# trill_slim.net
KiCad netlist of a schematic drawn in EAGLE
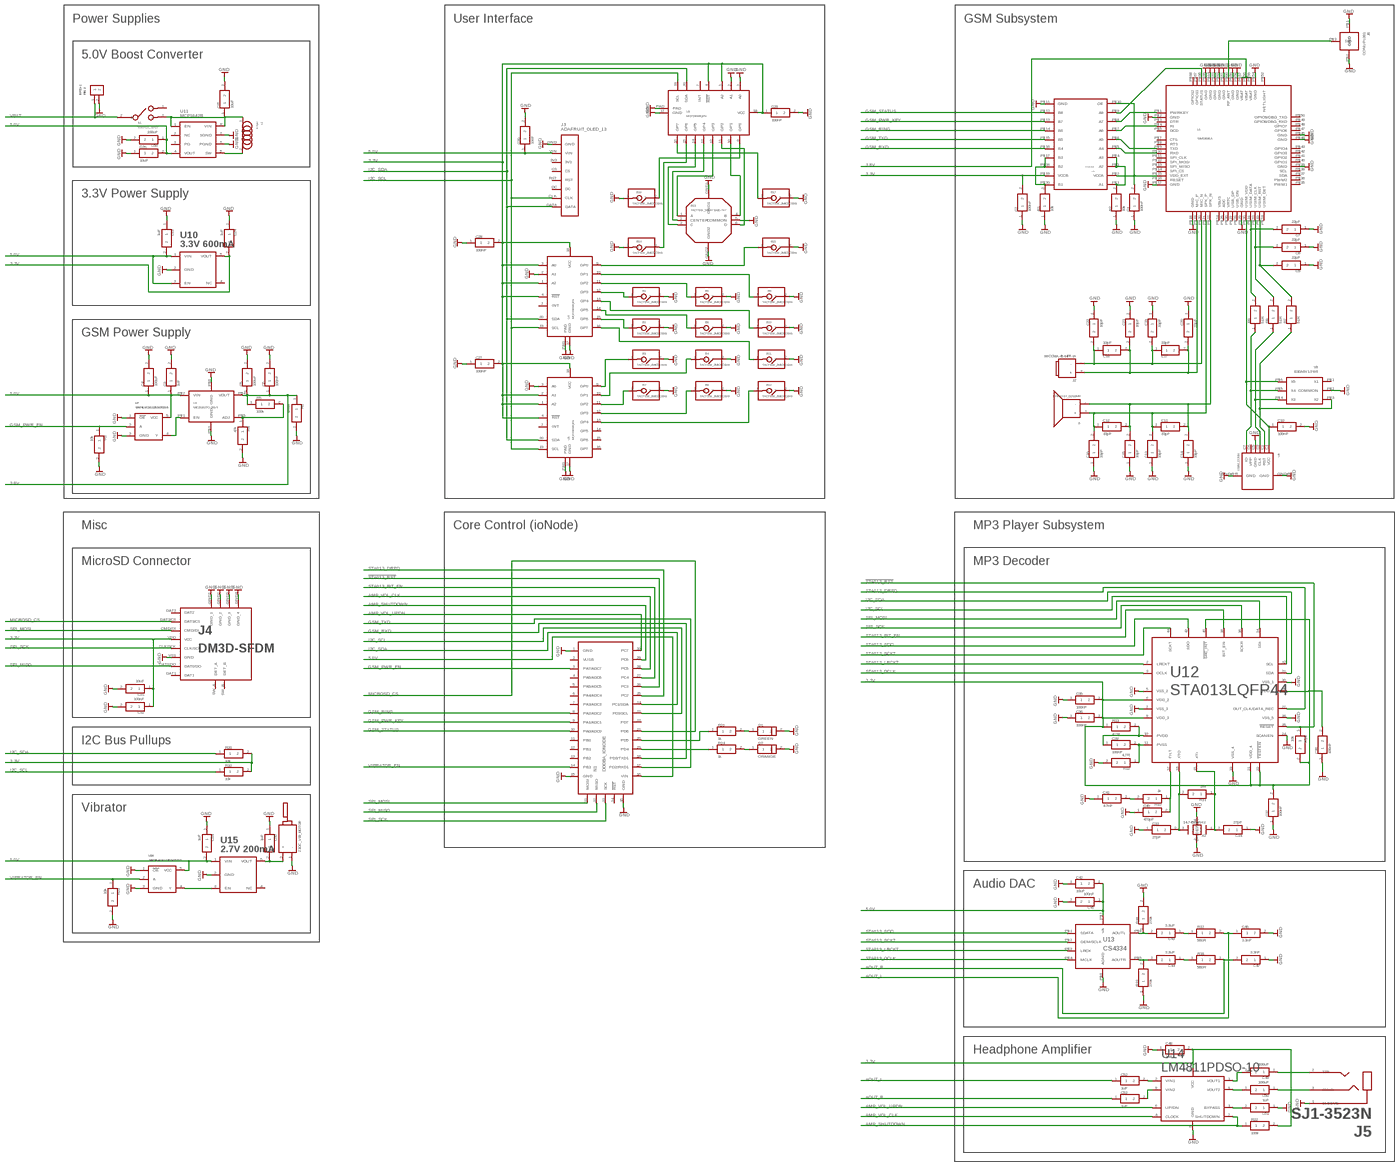
[diagram p0: schematic, sheet 1, overview]
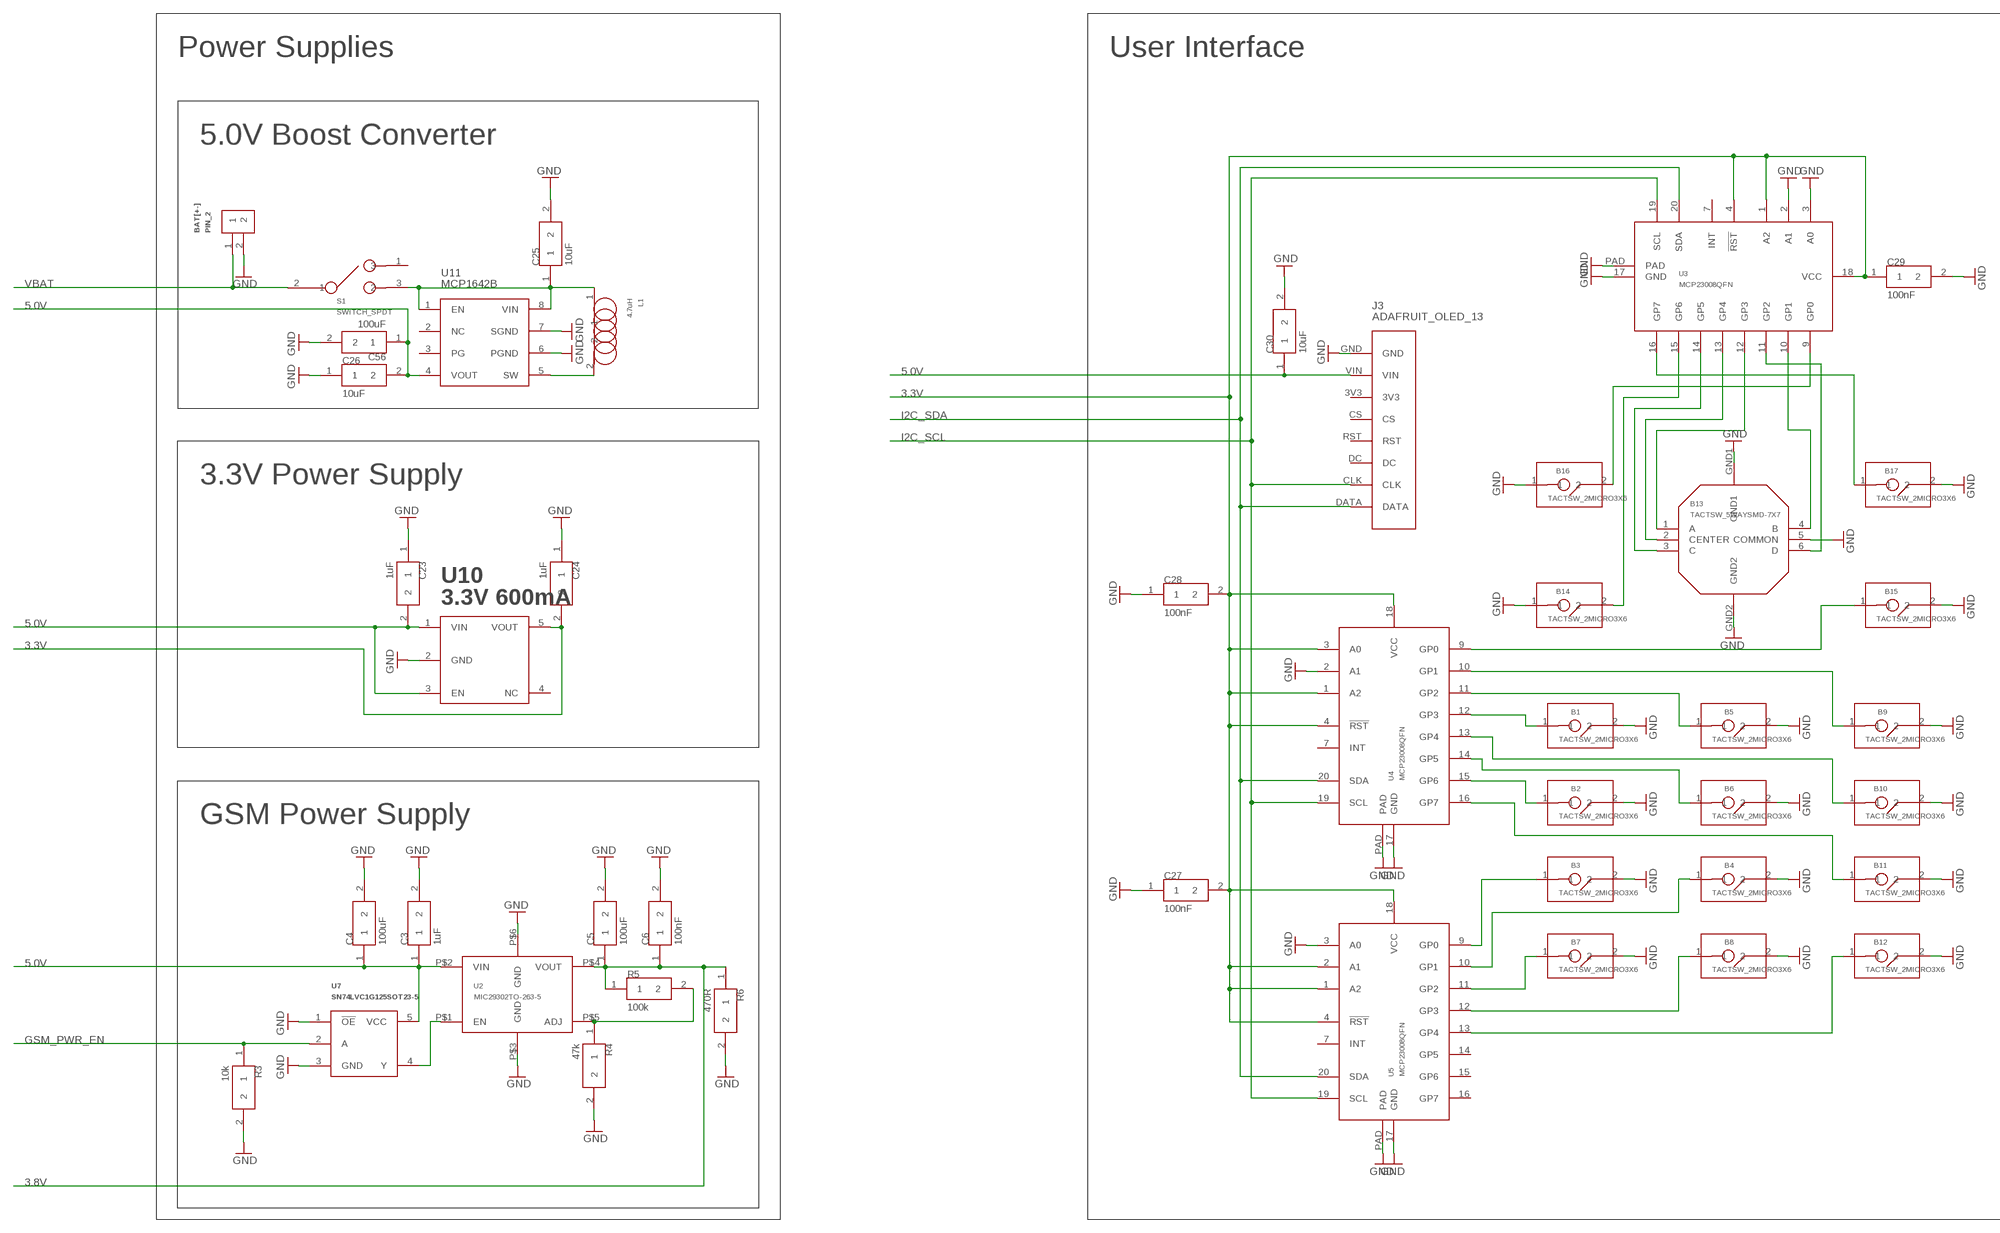
[diagram p1: schematic, sheet 1, part 1 of 4]
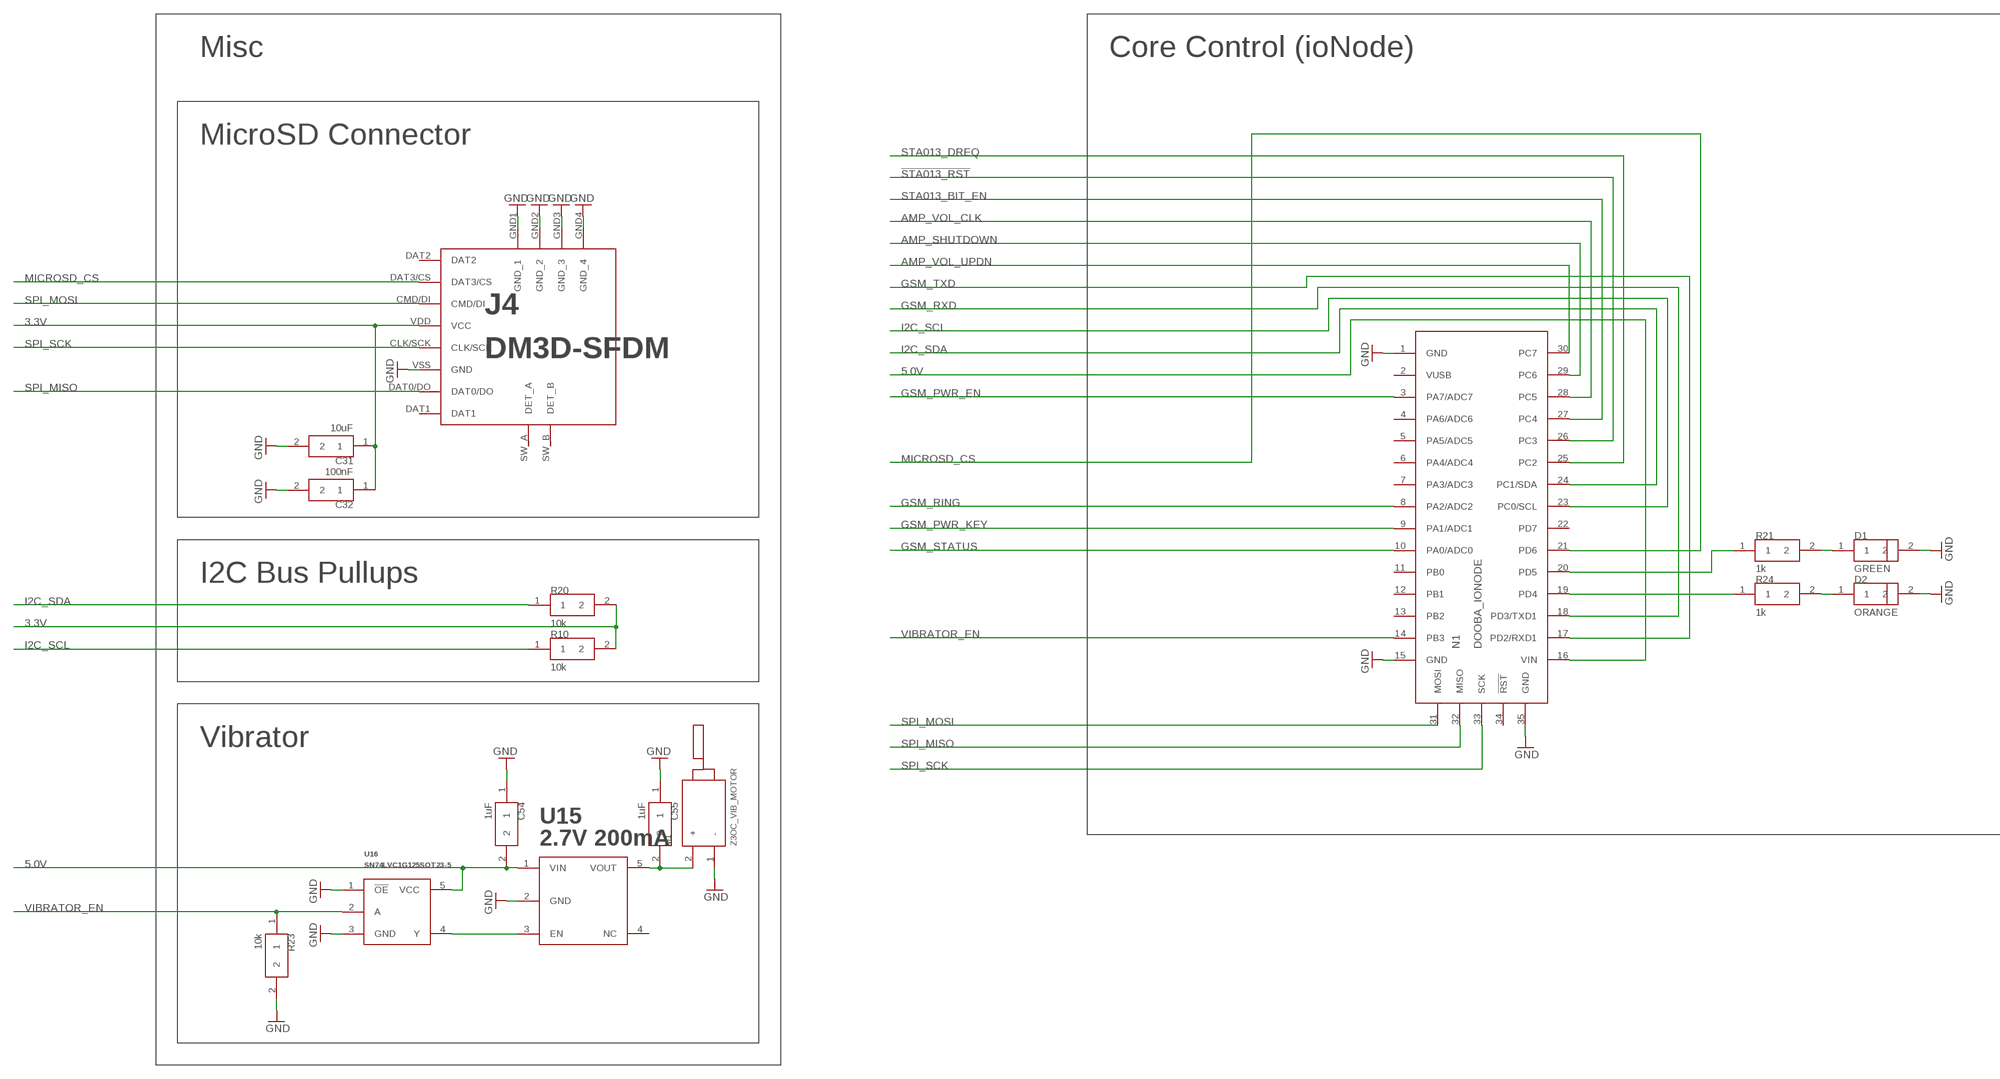
[diagram p2: schematic, sheet 1, part 2 of 4]
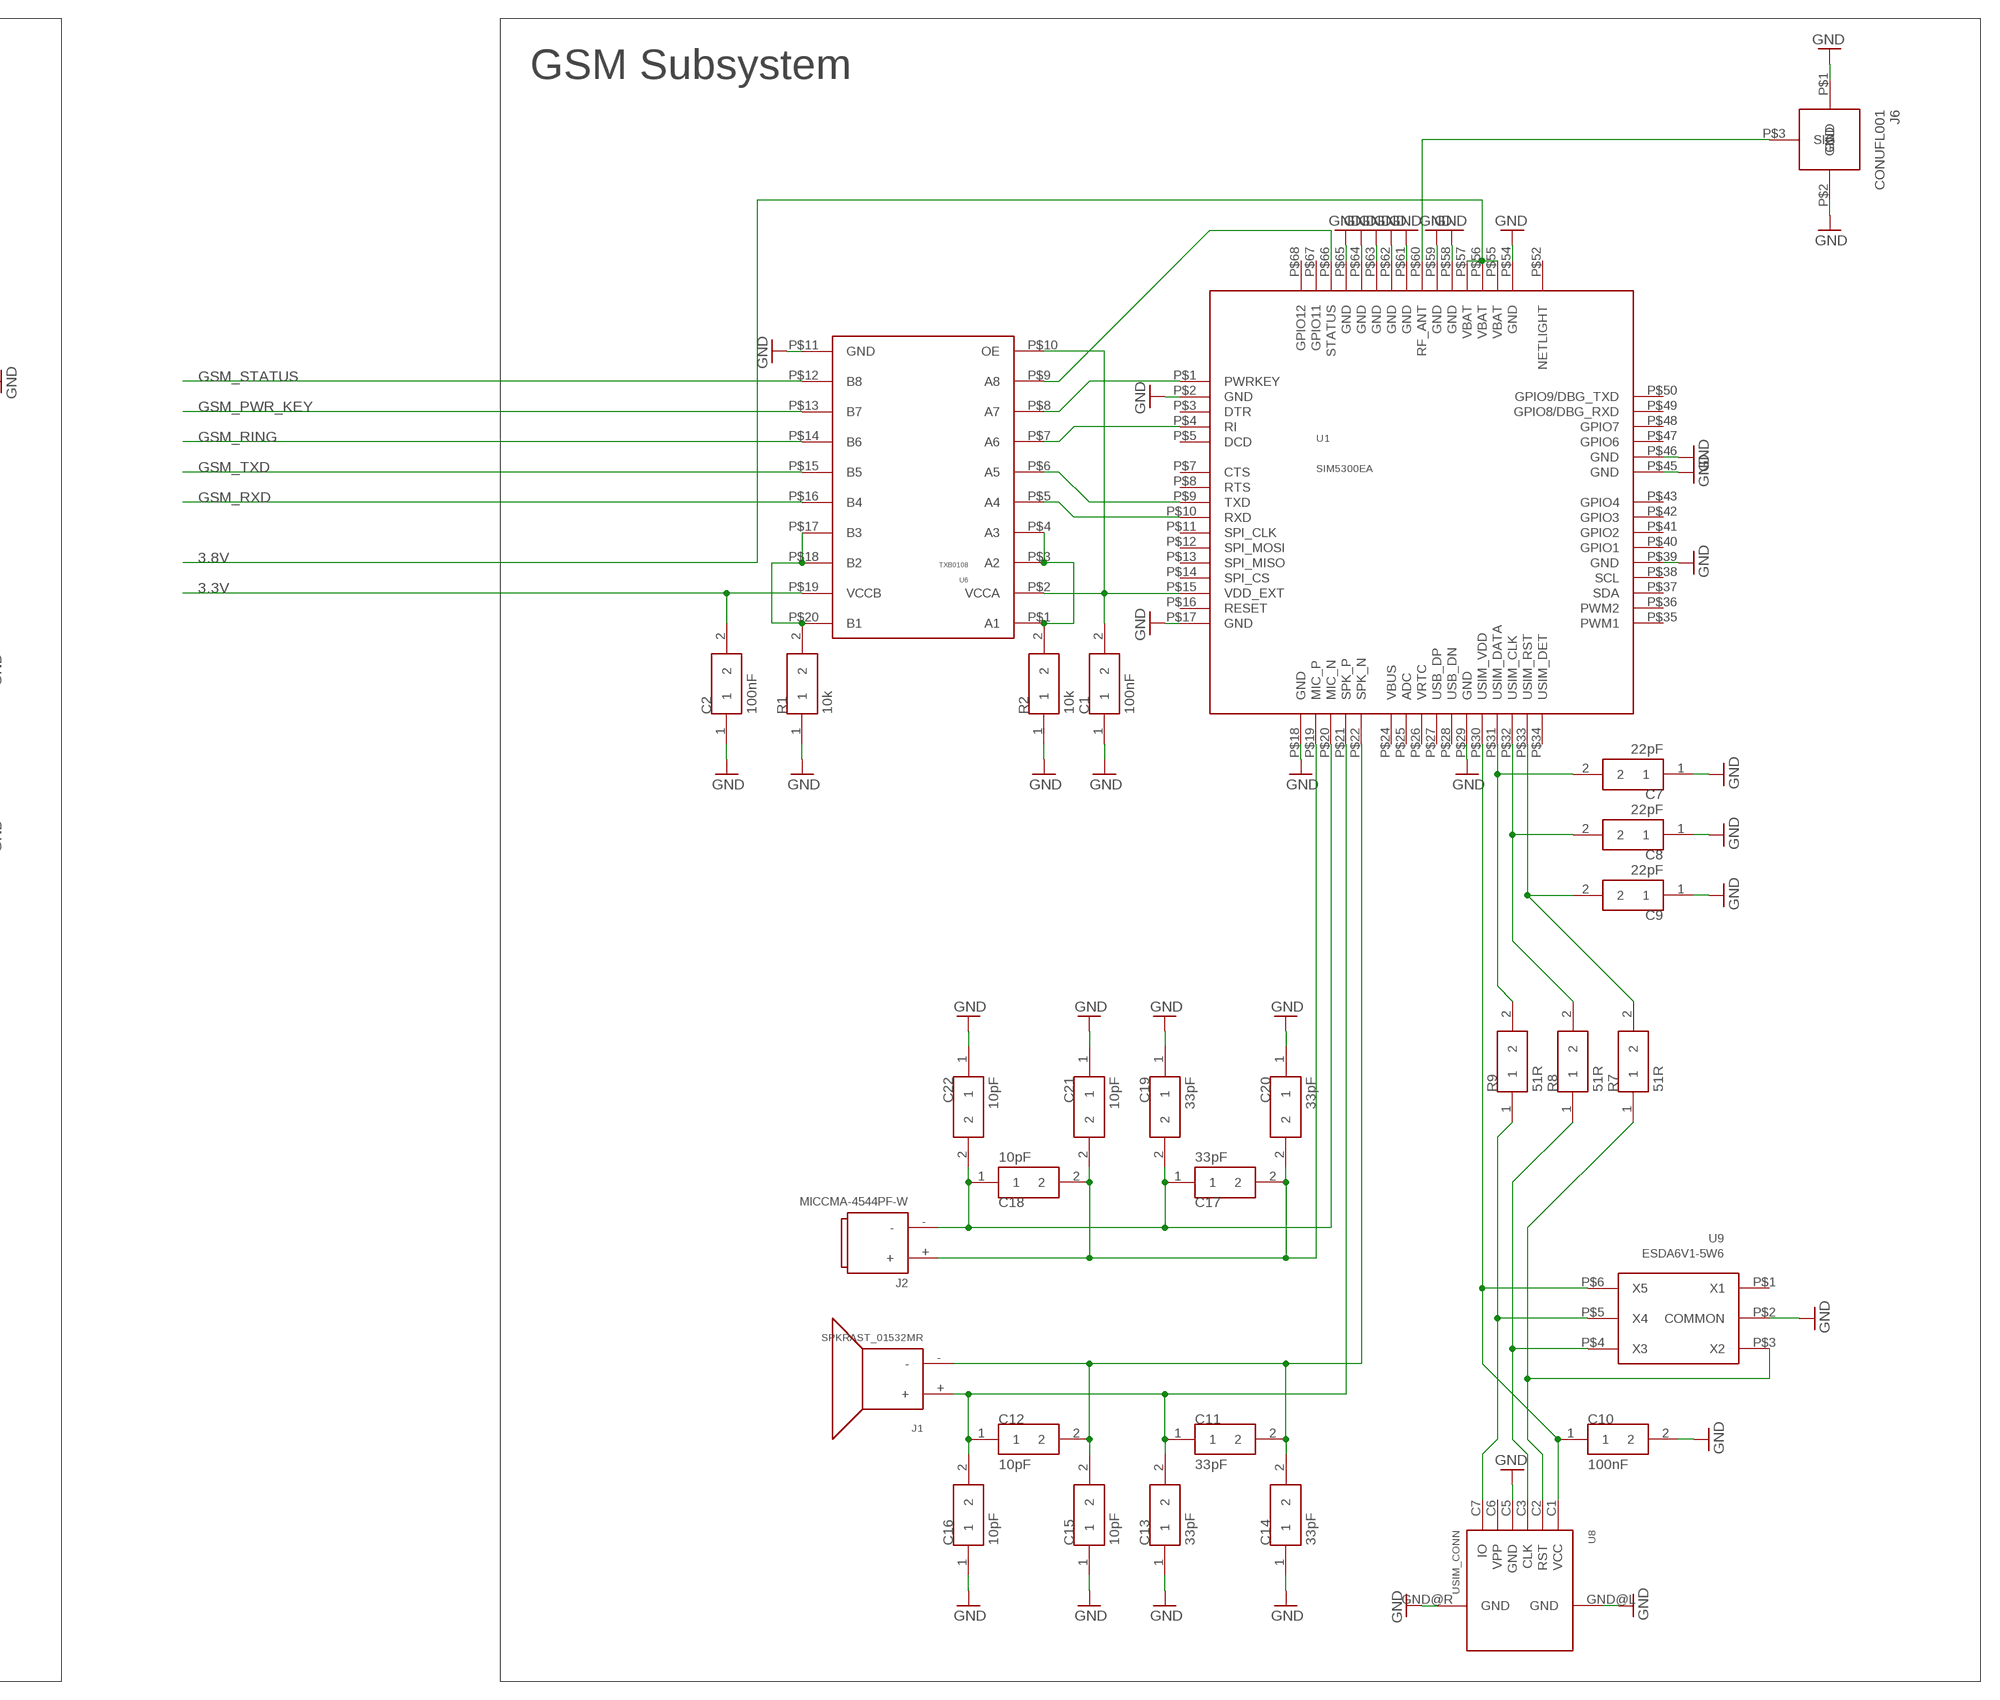
[diagram p3: schematic, sheet 1, part 3 of 4]
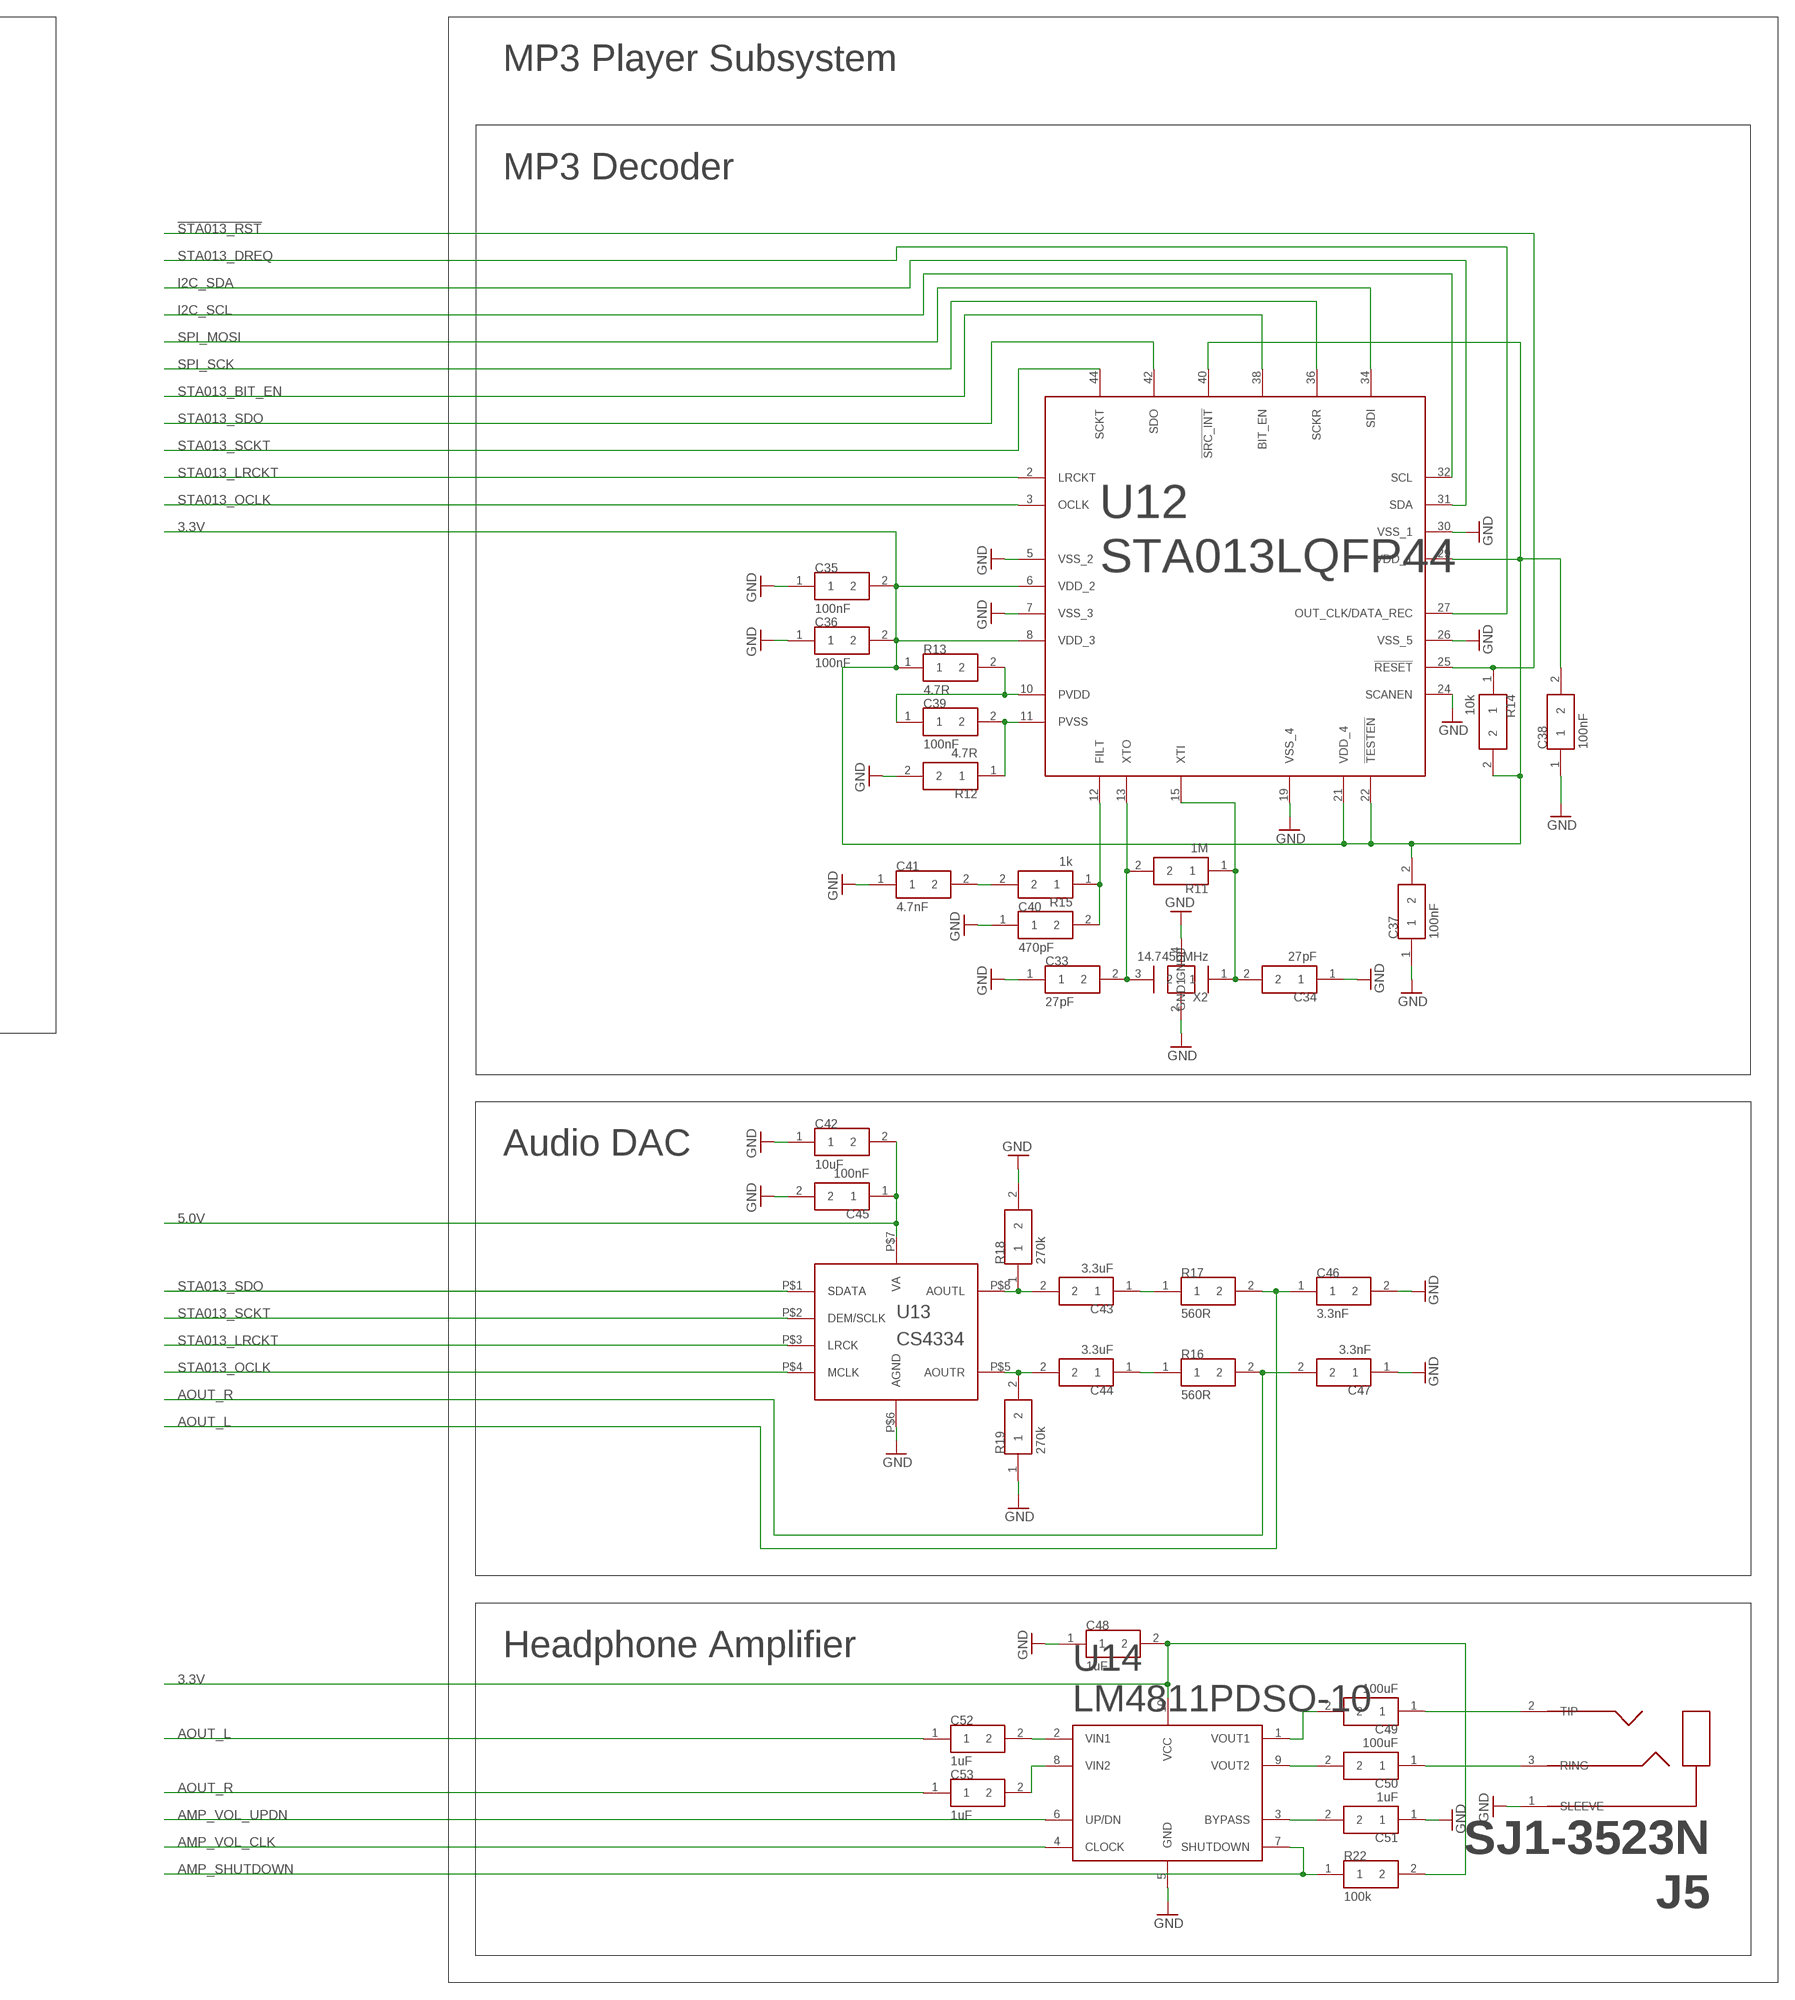
[diagram p4: schematic, sheet 1, part 4 of 4]

(export (version "E")
  (design (tool "Eeschema 10.0.6"))
  (components
    (comp (ref "B1")
      (value "TACTSW_2MICRO3X6")
      (footprint "eagle-import:TACTSW_MICRO3X6")
      (libsource (lib "eagle-import") (part "TACTSW_2MICRO3X6"))
    )
    (comp (ref "B2")
      (value "TACTSW_2MICRO3X6")
      (footprint "eagle-import:TACTSW_MICRO3X6")
      (libsource (lib "eagle-import") (part "TACTSW_2MICRO3X6"))
    )
    (comp (ref "B3")
      (value "TACTSW_2MICRO3X6")
      (footprint "eagle-import:TACTSW_MICRO3X6")
      (libsource (lib "eagle-import") (part "TACTSW_2MICRO3X6"))
    )
    (comp (ref "B4")
      (value "TACTSW_2MICRO3X6")
      (footprint "eagle-import:TACTSW_MICRO3X6")
      (libsource (lib "eagle-import") (part "TACTSW_2MICRO3X6"))
    )
    (comp (ref "B5")
      (value "TACTSW_2MICRO3X6")
      (footprint "eagle-import:TACTSW_MICRO3X6")
      (libsource (lib "eagle-import") (part "TACTSW_2MICRO3X6"))
    )
    (comp (ref "B6")
      (value "TACTSW_2MICRO3X6")
      (footprint "eagle-import:TACTSW_MICRO3X6")
      (libsource (lib "eagle-import") (part "TACTSW_2MICRO3X6"))
    )
    (comp (ref "B7")
      (value "TACTSW_2MICRO3X6")
      (footprint "eagle-import:TACTSW_MICRO3X6")
      (libsource (lib "eagle-import") (part "TACTSW_2MICRO3X6"))
    )
    (comp (ref "B8")
      (value "TACTSW_2MICRO3X6")
      (footprint "eagle-import:TACTSW_MICRO3X6")
      (libsource (lib "eagle-import") (part "TACTSW_2MICRO3X6"))
    )
    (comp (ref "B9")
      (value "TACTSW_2MICRO3X6")
      (footprint "eagle-import:TACTSW_MICRO3X6")
      (libsource (lib "eagle-import") (part "TACTSW_2MICRO3X6"))
    )
    (comp (ref "B10")
      (value "TACTSW_2MICRO3X6")
      (footprint "eagle-import:TACTSW_MICRO3X6")
      (libsource (lib "eagle-import") (part "TACTSW_2MICRO3X6"))
    )
    (comp (ref "B11")
      (value "TACTSW_2MICRO3X6")
      (footprint "eagle-import:TACTSW_MICRO3X6")
      (libsource (lib "eagle-import") (part "TACTSW_2MICRO3X6"))
    )
    (comp (ref "B12")
      (value "TACTSW_2MICRO3X6")
      (footprint "eagle-import:TACTSW_MICRO3X6")
      (libsource (lib "eagle-import") (part "TACTSW_2MICRO3X6"))
    )
    (comp (ref "B13")
      (value "TACTSW_5WAYSMD-7X7")
      (footprint "eagle-import:TACTSW-5WAY-7X7")
      (libsource (lib "eagle-import") (part "TACTSW_5WAYSMD-7X7"))
    )
    (comp (ref "B14")
      (value "TACTSW_2MICRO3X6")
      (footprint "eagle-import:TACTSW_MICRO3X6")
      (libsource (lib "eagle-import") (part "TACTSW_2MICRO3X6"))
    )
    (comp (ref "B15")
      (value "TACTSW_2MICRO3X6")
      (footprint "eagle-import:TACTSW_MICRO3X6")
      (libsource (lib "eagle-import") (part "TACTSW_2MICRO3X6"))
    )
    (comp (ref "B16")
      (value "TACTSW_2MICRO3X6")
      (footprint "eagle-import:TACTSW_MICRO3X6")
      (libsource (lib "eagle-import") (part "TACTSW_2MICRO3X6"))
    )
    (comp (ref "B17")
      (value "TACTSW_2MICRO3X6")
      (footprint "eagle-import:TACTSW_MICRO3X6")
      (libsource (lib "eagle-import") (part "TACTSW_2MICRO3X6"))
    )
    (comp (ref "BAT[+-]")
      (value "PIN_2")
      (footprint "eagle-import:PIN_2")
      (libsource (lib "eagle-import") (part "PIN_2"))
    )
    (comp (ref "C1")
      (value "100nF")
      (footprint "eagle-import:0805")
      (libsource (lib "eagle-import") (part "CAP0805"))
    )
    (comp (ref "C2")
      (value "100nF")
      (footprint "eagle-import:0805")
      (libsource (lib "eagle-import") (part "CAP0805"))
    )
    (comp (ref "C3")
      (value "1uF")
      (footprint "eagle-import:0805")
      (libsource (lib "eagle-import") (part "CAP0805"))
    )
    (comp (ref "C4")
      (value "100uF")
      (footprint "eagle-import:1210")
      (libsource (lib "eagle-import") (part "CAP1210"))
    )
    (comp (ref "C5")
      (value "100uF")
      (footprint "eagle-import:1210")
      (libsource (lib "eagle-import") (part "CAP1210"))
    )
    (comp (ref "C6")
      (value "100nF")
      (footprint "eagle-import:0805")
      (libsource (lib "eagle-import") (part "CAP0805"))
    )
    (comp (ref "C7")
      (value "22pF")
      (footprint "eagle-import:0805")
      (libsource (lib "eagle-import") (part "CAP0805"))
    )
    (comp (ref "C8")
      (value "22pF")
      (footprint "eagle-import:0805")
      (libsource (lib "eagle-import") (part "CAP0805"))
    )
    (comp (ref "C9")
      (value "22pF")
      (footprint "eagle-import:0805")
      (libsource (lib "eagle-import") (part "CAP0805"))
    )
    (comp (ref "C10")
      (value "100nF")
      (footprint "eagle-import:0805")
      (libsource (lib "eagle-import") (part "CAP0805"))
    )
    (comp (ref "C11")
      (value "33pF")
      (footprint "eagle-import:0805")
      (libsource (lib "eagle-import") (part "CAP0805"))
    )
    (comp (ref "C12")
      (value "10pF")
      (footprint "eagle-import:0805")
      (libsource (lib "eagle-import") (part "CAP0805"))
    )
    (comp (ref "C13")
      (value "33pF")
      (footprint "eagle-import:0805")
      (libsource (lib "eagle-import") (part "CAP0805"))
    )
    (comp (ref "C14")
      (value "33pF")
      (footprint "eagle-import:0805")
      (libsource (lib "eagle-import") (part "CAP0805"))
    )
    (comp (ref "C15")
      (value "10pF")
      (footprint "eagle-import:0805")
      (libsource (lib "eagle-import") (part "CAP0805"))
    )
    (comp (ref "C16")
      (value "10pF")
      (footprint "eagle-import:0805")
      (libsource (lib "eagle-import") (part "CAP0805"))
    )
    (comp (ref "C17")
      (value "33pF")
      (footprint "eagle-import:0805")
      (libsource (lib "eagle-import") (part "CAP0805"))
    )
    (comp (ref "C18")
      (value "10pF")
      (footprint "eagle-import:0805")
      (libsource (lib "eagle-import") (part "CAP0805"))
    )
    (comp (ref "C19")
      (value "33pF")
      (footprint "eagle-import:0805")
      (libsource (lib "eagle-import") (part "CAP0805"))
    )
    (comp (ref "C20")
      (value "33pF")
      (footprint "eagle-import:0805")
      (libsource (lib "eagle-import") (part "CAP0805"))
    )
    (comp (ref "C21")
      (value "10pF")
      (footprint "eagle-import:0805")
      (libsource (lib "eagle-import") (part "CAP0805"))
    )
    (comp (ref "C22")
      (value "10pF")
      (footprint "eagle-import:0805")
      (libsource (lib "eagle-import") (part "CAP0805"))
    )
    (comp (ref "C23")
      (value "1uF")
      (footprint "eagle-import:0805")
      (libsource (lib "eagle-import") (part "CAP0805"))
    )
    (comp (ref "C24")
      (value "1uF")
      (footprint "eagle-import:0805")
      (libsource (lib "eagle-import") (part "CAP0805"))
    )
    (comp (ref "C25")
      (value "10uF")
      (footprint "eagle-import:0805")
      (libsource (lib "eagle-import") (part "CAP0805"))
    )
    (comp (ref "C26")
      (value "10uF")
      (footprint "eagle-import:0805")
      (libsource (lib "eagle-import") (part "CAP0805"))
    )
    (comp (ref "C27")
      (value "100nF")
      (footprint "eagle-import:0805")
      (libsource (lib "eagle-import") (part "CAP0805"))
    )
    (comp (ref "C28")
      (value "100nF")
      (footprint "eagle-import:0805")
      (libsource (lib "eagle-import") (part "CAP0805"))
    )
    (comp (ref "C29")
      (value "100nF")
      (footprint "eagle-import:0805")
      (libsource (lib "eagle-import") (part "CAP0805"))
    )
    (comp (ref "C30")
      (value "10uF")
      (footprint "eagle-import:0805")
      (libsource (lib "eagle-import") (part "CAP0805"))
    )
    (comp (ref "C31")
      (value "10uF")
      (footprint "eagle-import:0805")
      (libsource (lib "eagle-import") (part "CAP0805"))
    )
    (comp (ref "C32")
      (value "100nF")
      (footprint "eagle-import:0805")
      (libsource (lib "eagle-import") (part "CAP0805"))
    )
    (comp (ref "C33")
      (value "27pF")
      (footprint "eagle-import:0805")
      (libsource (lib "eagle-import") (part "CAP0805"))
    )
    (comp (ref "C34")
      (value "27pF")
      (footprint "eagle-import:0805")
      (libsource (lib "eagle-import") (part "CAP0805"))
    )
    (comp (ref "C35")
      (value "100nF")
      (footprint "eagle-import:0805")
      (libsource (lib "eagle-import") (part "CAP0805"))
    )
    (comp (ref "C36")
      (value "100nF")
      (footprint "eagle-import:0805")
      (libsource (lib "eagle-import") (part "CAP0805"))
    )
    (comp (ref "C37")
      (value "100nF")
      (footprint "eagle-import:0805")
      (libsource (lib "eagle-import") (part "CAP0805"))
    )
    (comp (ref "C38")
      (value "100nF")
      (footprint "eagle-import:0805")
      (libsource (lib "eagle-import") (part "CAP0805"))
    )
    (comp (ref "C39")
      (value "100nF")
      (footprint "eagle-import:0805")
      (libsource (lib "eagle-import") (part "CAP0805"))
    )
    (comp (ref "C40")
      (value "470pF")
      (footprint "eagle-import:0805")
      (libsource (lib "eagle-import") (part "CAP0805"))
    )
    (comp (ref "C41")
      (value "4.7nF")
      (footprint "eagle-import:0805")
      (libsource (lib "eagle-import") (part "CAP0805"))
    )
    (comp (ref "C42")
      (value "10uF")
      (footprint "eagle-import:0805")
      (libsource (lib "eagle-import") (part "CAP0805"))
    )
    (comp (ref "C43")
      (value "3.3uF")
      (footprint "eagle-import:0805")
      (libsource (lib "eagle-import") (part "CAP0805"))
    )
    (comp (ref "C44")
      (value "3.3uF")
      (footprint "eagle-import:0805")
      (libsource (lib "eagle-import") (part "CAP0805"))
    )
    (comp (ref "C45")
      (value "100nF")
      (footprint "eagle-import:0805")
      (libsource (lib "eagle-import") (part "CAP0805"))
    )
    (comp (ref "C46")
      (value "3.3nF")
      (footprint "eagle-import:0805")
      (libsource (lib "eagle-import") (part "CAP0805"))
    )
    (comp (ref "C47")
      (value "3.3nF")
      (footprint "eagle-import:0805")
      (libsource (lib "eagle-import") (part "CAP0805"))
    )
    (comp (ref "C48")
      (value "1uF")
      (footprint "eagle-import:0805")
      (libsource (lib "eagle-import") (part "CAP0805"))
    )
    (comp (ref "C49")
      (value "100uF")
      (footprint "eagle-import:1210")
      (libsource (lib "eagle-import") (part "CAP1210"))
    )
    (comp (ref "C50")
      (value "100uF")
      (footprint "eagle-import:1210")
      (libsource (lib "eagle-import") (part "CAP1210"))
    )
    (comp (ref "C51")
      (value "1uF")
      (footprint "eagle-import:0805")
      (libsource (lib "eagle-import") (part "CAP0805"))
    )
    (comp (ref "C52")
      (value "1uF")
      (footprint "eagle-import:0805")
      (libsource (lib "eagle-import") (part "CAP0805"))
    )
    (comp (ref "C53")
      (value "1uF")
      (footprint "eagle-import:0805")
      (libsource (lib "eagle-import") (part "CAP0805"))
    )
    (comp (ref "C54")
      (value "1uF")
      (footprint "eagle-import:0805")
      (libsource (lib "eagle-import") (part "CAP0805"))
    )
    (comp (ref "C55")
      (value "1uF")
      (footprint "eagle-import:0805")
      (libsource (lib "eagle-import") (part "CAP0805"))
    )
    (comp (ref "C56")
      (value "100uF")
      (footprint "eagle-import:1210")
      (libsource (lib "eagle-import") (part "CAP1210"))
    )
    (comp (ref "D1")
      (value "GREEN")
      (footprint "eagle-import:0805")
      (libsource (lib "eagle-import") (part "LED0805"))
    )
    (comp (ref "D2")
      (value "ORANGE")
      (footprint "eagle-import:0805")
      (libsource (lib "eagle-import") (part "LED0805"))
    )
    (comp (ref "J1")
      (value "SPKRAST_01532MR")
      (footprint "eagle-import:SPKR_AST_01532MR")
      (libsource (lib "eagle-import") (part "SPKRAST_01532MR"))
    )
    (comp (ref "J2")
      (value "MICCMA-4544PF-W")
      (footprint "eagle-import:MIC_CMA-4544PF-W")
      (libsource (lib "eagle-import") (part "MICCMA-4544PF-W"))
    )
    (comp (ref "J3")
      (value "ADAFRUIT_OLED_13")
      (footprint "eagle-import:ADAFRUIT_OLED_13")
      (libsource (lib "eagle-import") (part "ADAFRUIT_OLED_13"))
    )
    (comp (ref "J4")
      (value "DM3D-SFDM")
      (footprint "eagle-import:DM3D-SF")
      (libsource (lib "eagle-import") (part "DM3D-SFDM"))
    )
    (comp (ref "J5")
      (value "SJ1-3523N")
      (footprint "eagle-import:SJ1-352XN")
      (libsource (lib "eagle-import") (part "SJ1-3523N"))
    )
    (comp (ref "J6")
      (value "CONUFL001")
      (footprint "eagle-import:CONUFL001")
      (libsource (lib "eagle-import") (part "CONUFL001"))
    )
    (comp (ref "L1")
      (value "4.7uH")
      (footprint "eagle-import:2520")
      (libsource (lib "eagle-import") (part "IND2520"))
    )
    (comp (ref "M1")
      (value "Z3OC_VIB_MOTOR")
      (footprint "eagle-import:Z3OC_VIB_MOTOR")
      (libsource (lib "eagle-import") (part "Z3OC_VIB_MOTOR"))
    )
    (comp (ref "N1")
      (value "DOOBA_IONODE")
      (footprint "eagle-import:DOOBA_IONODE")
      (libsource (lib "eagle-import") (part "DOOBA_IONODE"))
    )
    (comp (ref "R1")
      (value "10k")
      (footprint "eagle-import:0805")
      (libsource (lib "eagle-import") (part "RES0805"))
    )
    (comp (ref "R2")
      (value "10k")
      (footprint "eagle-import:0805")
      (libsource (lib "eagle-import") (part "RES0805"))
    )
    (comp (ref "R3")
      (value "10k")
      (footprint "eagle-import:0805")
      (libsource (lib "eagle-import") (part "RES0805"))
    )
    (comp (ref "R4")
      (value "47k")
      (footprint "eagle-import:0805")
      (libsource (lib "eagle-import") (part "RES0805"))
    )
    (comp (ref "R5")
      (value "100k")
      (footprint "eagle-import:0805")
      (libsource (lib "eagle-import") (part "RES0805"))
    )
    (comp (ref "R6")
      (value "470R")
      (footprint "eagle-import:0805")
      (libsource (lib "eagle-import") (part "RES0805"))
    )
    (comp (ref "R7")
      (value "51R")
      (footprint "eagle-import:0805")
      (libsource (lib "eagle-import") (part "RES0805"))
    )
    (comp (ref "R8")
      (value "51R")
      (footprint "eagle-import:0805")
      (libsource (lib "eagle-import") (part "RES0805"))
    )
    (comp (ref "R9")
      (value "51R")
      (footprint "eagle-import:0805")
      (libsource (lib "eagle-import") (part "RES0805"))
    )
    (comp (ref "R10")
      (value "10k")
      (footprint "eagle-import:0805")
      (libsource (lib "eagle-import") (part "RES0805"))
    )
    (comp (ref "R11")
      (value "1M")
      (footprint "eagle-import:0805")
      (libsource (lib "eagle-import") (part "RES0805"))
    )
    (comp (ref "R12")
      (value "4.7R")
      (footprint "eagle-import:0805")
      (libsource (lib "eagle-import") (part "RES0805"))
    )
    (comp (ref "R13")
      (value "4.7R")
      (footprint "eagle-import:0805")
      (libsource (lib "eagle-import") (part "RES0805"))
    )
    (comp (ref "R14")
      (value "10k")
      (footprint "eagle-import:0805")
      (libsource (lib "eagle-import") (part "RES0805"))
    )
    (comp (ref "R15")
      (value "1k")
      (footprint "eagle-import:0805")
      (libsource (lib "eagle-import") (part "RES0805"))
    )
    (comp (ref "R16")
      (value "560R")
      (footprint "eagle-import:0805")
      (libsource (lib "eagle-import") (part "RES0805"))
    )
    (comp (ref "R17")
      (value "560R")
      (footprint "eagle-import:0805")
      (libsource (lib "eagle-import") (part "RES0805"))
    )
    (comp (ref "R18")
      (value "270k")
      (footprint "eagle-import:0805")
      (libsource (lib "eagle-import") (part "RES0805"))
    )
    (comp (ref "R19")
      (value "270k")
      (footprint "eagle-import:0805")
      (libsource (lib "eagle-import") (part "RES0805"))
    )
    (comp (ref "R20")
      (value "10k")
      (footprint "eagle-import:0805")
      (libsource (lib "eagle-import") (part "RES0805"))
    )
    (comp (ref "R21")
      (value "1k")
      (footprint "eagle-import:0805")
      (libsource (lib "eagle-import") (part "RES0805"))
    )
    (comp (ref "R22")
      (value "100k")
      (footprint "eagle-import:0805")
      (libsource (lib "eagle-import") (part "RES0805"))
    )
    (comp (ref "R23")
      (value "10k")
      (footprint "eagle-import:0805")
      (libsource (lib "eagle-import") (part "RES0805"))
    )
    (comp (ref "R24")
      (value "1k")
      (footprint "eagle-import:0805")
      (libsource (lib "eagle-import") (part "RES0805"))
    )
    (comp (ref "S1")
      (value "SWITCH_SPDT")
      (footprint "eagle-import:JS102011")
      (libsource (lib "eagle-import") (part "SWITCH_SPDT"))
    )
    (comp (ref "U1")
      (value "SIM5300EA")
      (footprint "eagle-import:SIM5300")
      (libsource (lib "eagle-import") (part "SIM5300EA"))
    )
    (comp (ref "U2")
      (value "MIC29302TO-263-5")
      (footprint "eagle-import:TO-263")
      (libsource (lib "eagle-import") (part "MIC29302TO-263-5"))
    )
    (comp (ref "U3")
      (value "MCP23008QFN")
      (footprint "eagle-import:20-VQFN")
      (libsource (lib "eagle-import") (part "MCP23008QFN"))
    )
    (comp (ref "U4")
      (value "MCP23008QFN")
      (footprint "eagle-import:20-VQFN")
      (libsource (lib "eagle-import") (part "MCP23008QFN"))
    )
    (comp (ref "U5")
      (value "MCP23008QFN")
      (footprint "eagle-import:20-VQFN")
      (libsource (lib "eagle-import") (part "MCP23008QFN"))
    )
    (comp (ref "U6")
      (value "TXB0108")
      (footprint "eagle-import:TSSOP-20")
      (libsource (lib "eagle-import") (part "TXB0108"))
    )
    (comp (ref "U7")
      (value "SN74LVC1G125SOT23-5")
      (footprint "eagle-import:SOT23-5")
      (libsource (lib "eagle-import") (part "SN74LVC1G125SOT23-5"))
    )
    (comp (ref "U8")
      (value "USIM_CONN")
      (footprint "eagle-import:WE_USIM_HINGE")
      (libsource (lib "eagle-import") (part "USIM_CONN"))
    )
    (comp (ref "U9")
      (value "ESDA6V1-5W6")
      (footprint "eagle-import:SOT-323-6L")
      (libsource (lib "eagle-import") (part "ESDA6V1-5W6"))
    )
    (comp (ref "U10")
      (value "3.3V 600mA")
      (footprint "eagle-import:SOT23-5")
      (libsource (lib "eagle-import") (part "LP3985SOT23-5"))
    )
    (comp (ref "U11")
      (value "MCP1642B")
      (footprint "eagle-import:MSOP8")
      (libsource (lib "eagle-import") (part "MCP1642B"))
    )
    (comp (ref "U12")
      (value "STA013LQFP44")
      (footprint "eagle-import:QFP44")
      (libsource (lib "eagle-import") (part "STA013LQFP44"))
    )
    (comp (ref "U13")
      (value "CS4334")
      (footprint "eagle-import:SO8")
      (libsource (lib "eagle-import") (part "CS4334"))
    )
    (comp (ref "U14")
      (value "LM4811PDSO-10")
      (footprint "eagle-import:PDSO-10")
      (libsource (lib "eagle-import") (part "LM4811PDSO-10"))
    )
    (comp (ref "U15")
      (value "2.7V 200mA")
      (footprint "eagle-import:SOT23-5")
      (libsource (lib "eagle-import") (part "LP3985SOT23-5"))
    )
    (comp (ref "U16")
      (value "SN74LVC1G125SOT23-5")
      (footprint "eagle-import:SOT23-5")
      (libsource (lib "eagle-import") (part "SN74LVC1G125SOT23-5"))
    )
    (comp (ref "X2")
      (value "14.7456MHz")
      (footprint "eagle-import:XTAL_3225")
      (libsource (lib "eagle-import") (part "XTAL_GNDSMD_3225"))
    )
  )
  (nets
    (net (code "1") (name "/3.3V") (class "Default")
      (node (ref "C2") (pin "2") (pinfunction "2_2") (pintype "bidirectional"))
      (node (ref "C24") (pin "2") (pinfunction "2_2") (pintype "bidirectional"))
      (node (ref "C27") (pin "2") (pinfunction "2_2") (pintype "bidirectional"))
      (node (ref "C28") (pin "2") (pinfunction "2_2") (pintype "bidirectional"))
      (node (ref "C29") (pin "1") (pinfunction "1_1") (pintype "bidirectional"))
      (node (ref "C31") (pin "1") (pinfunction "1_1") (pintype "bidirectional"))
      (node (ref "C32") (pin "1") (pinfunction "1_1") (pintype "bidirectional"))
      (node (ref "C35") (pin "2") (pinfunction "2_2") (pintype "bidirectional"))
      (node (ref "C36") (pin "2") (pinfunction "2_2") (pintype "bidirectional"))
      (node (ref "C37") (pin "2") (pinfunction "2_2") (pintype "bidirectional"))
      (node (ref "C38") (pin "2") (pinfunction "2_2") (pintype "bidirectional"))
      (node (ref "C48") (pin "2") (pinfunction "2_2") (pintype "bidirectional"))
      (node (ref "J4") (pin "VDD") (pinfunction "VCC_VDD") (pintype "bidirectional"))
      (node (ref "R10") (pin "2") (pinfunction "2_2") (pintype "bidirectional"))
      (node (ref "R13") (pin "1") (pinfunction "1_1") (pintype "bidirectional"))
      (node (ref "R14") (pin "2") (pinfunction "2_2") (pintype "bidirectional"))
      (node (ref "R20") (pin "2") (pinfunction "2_2") (pintype "bidirectional"))
      (node (ref "R22") (pin "2") (pinfunction "2_2") (pintype "bidirectional"))
      (node (ref "U10") (pin "5") (pinfunction "VOUT_5") (pintype "bidirectional"))
      (node (ref "U12") (pin "21") (pinfunction "VDD_4_21") (pintype "bidirectional"))
      (node (ref "U12") (pin "22") (pinfunction "~{TESTEN}_22") (pintype "bidirectional"))
      (node (ref "U12") (pin "29") (pinfunction "VDD_1_29") (pintype "bidirectional"))
      (node (ref "U12") (pin "40") (pinfunction "~{SRC_INT}_40") (pintype "bidirectional"))
      (node (ref "U12") (pin "6") (pinfunction "VDD_2_6") (pintype "bidirectional"))
      (node (ref "U12") (pin "8") (pinfunction "VDD_3_8") (pintype "bidirectional"))
      (node (ref "U14") (pin "10") (pinfunction "VCC_10") (pintype "bidirectional"))
      (node (ref "U3") (pin "1") (pinfunction "A2_1") (pintype "bidirectional"))
      (node (ref "U3") (pin "18") (pinfunction "VCC_18") (pintype "bidirectional"))
      (node (ref "U3") (pin "4") (pinfunction "~{RST}_4") (pintype "bidirectional"))
      (node (ref "U4") (pin "1") (pinfunction "A2_1") (pintype "bidirectional"))
      (node (ref "U4") (pin "18") (pinfunction "VCC_18") (pintype "bidirectional"))
      (node (ref "U4") (pin "3") (pinfunction "A0_3") (pintype "bidirectional"))
      (node (ref "U4") (pin "4") (pinfunction "~{RST}_4") (pintype "bidirectional"))
      (node (ref "U5") (pin "1") (pinfunction "A2_1") (pintype "bidirectional"))
      (node (ref "U5") (pin "18") (pinfunction "VCC_18") (pintype "bidirectional"))
      (node (ref "U5") (pin "2") (pinfunction "A1_2") (pintype "bidirectional"))
      (node (ref "U5") (pin "4") (pinfunction "~{RST}_4") (pintype "bidirectional"))
      (node (ref "U6") (pin "P$19") (pinfunction "VCCB_P$19") (pintype "bidirectional"))
    )
    (net (code "2") (name "/3.8V") (class "Default")
      (node (ref "C5") (pin "1") (pinfunction "1_1") (pintype "bidirectional"))
      (node (ref "C6") (pin "1") (pinfunction "1_1") (pintype "bidirectional"))
      (node (ref "R5") (pin "1") (pinfunction "1_1") (pintype "bidirectional"))
      (node (ref "R6") (pin "1") (pinfunction "1_1") (pintype "bidirectional"))
      (node (ref "U1") (pin "P$55") (pinfunction "VBAT_P$55") (pintype "bidirectional"))
      (node (ref "U1") (pin "P$56") (pinfunction "VBAT_P$56") (pintype "bidirectional"))
      (node (ref "U1") (pin "P$57") (pinfunction "VBAT_P$57") (pintype "bidirectional"))
      (node (ref "U2") (pin "P$4") (pinfunction "VOUT_P$4") (pintype "bidirectional"))
    )
    (net (code "3") (name "/5.0V") (class "Default")
      (node (ref "C23") (pin "2") (pinfunction "2_2") (pintype "bidirectional"))
      (node (ref "C26") (pin "2") (pinfunction "2_2") (pintype "bidirectional"))
      (node (ref "C3") (pin "1") (pinfunction "1_1") (pintype "bidirectional"))
      (node (ref "C30") (pin "1") (pinfunction "1_1") (pintype "bidirectional"))
      (node (ref "C4") (pin "1") (pinfunction "1_1") (pintype "bidirectional"))
      (node (ref "C42") (pin "2") (pinfunction "2_2") (pintype "bidirectional"))
      (node (ref "C45") (pin "1") (pinfunction "1_1") (pintype "bidirectional"))
      (node (ref "C54") (pin "2") (pinfunction "2_2") (pintype "bidirectional"))
      (node (ref "C56") (pin "1") (pinfunction "1_1") (pintype "bidirectional"))
      (node (ref "J3") (pin "VIN") (pinfunction "VIN_VIN") (pintype "bidirectional"))
      (node (ref "N1") (pin "16") (pinfunction "VIN_16") (pintype "bidirectional"))
      (node (ref "U10") (pin "1") (pinfunction "VIN_1") (pintype "bidirectional"))
      (node (ref "U10") (pin "3") (pinfunction "EN_3") (pintype "bidirectional"))
      (node (ref "U11") (pin "4") (pinfunction "VOUT_4") (pintype "bidirectional"))
      (node (ref "U13") (pin "P$7") (pinfunction "VA_P$7") (pintype "bidirectional"))
      (node (ref "U15") (pin "1") (pinfunction "VIN_1") (pintype "bidirectional"))
      (node (ref "U16") (pin "5") (pinfunction "VCC_5") (pintype "bidirectional"))
      (node (ref "U2") (pin "P$2") (pinfunction "VIN_P$2") (pintype "bidirectional"))
      (node (ref "U7") (pin "5") (pinfunction "VCC_5") (pintype "bidirectional"))
    )
    (net (code "4") (name "/AMP_SHUTDOWN") (class "Default")
      (node (ref "N1") (pin "29") (pinfunction "PC6_29") (pintype "bidirectional"))
      (node (ref "R22") (pin "1") (pinfunction "1_1") (pintype "bidirectional"))
      (node (ref "U14") (pin "7") (pinfunction "SHUTDOWN_7") (pintype "bidirectional"))
    )
    (net (code "5") (name "/AMP_VOL_CLK") (class "Default")
      (node (ref "N1") (pin "28") (pinfunction "PC5_28") (pintype "bidirectional"))
      (node (ref "U14") (pin "4") (pinfunction "CLOCK_4") (pintype "bidirectional"))
    )
    (net (code "6") (name "/AMP_VOL_UPDN") (class "Default")
      (node (ref "N1") (pin "30") (pinfunction "PC7_30") (pintype "bidirectional"))
      (node (ref "U14") (pin "6") (pinfunction "UP/DN_6") (pintype "bidirectional"))
    )
    (net (code "7") (name "/AOUT_L") (class "Default")
      (node (ref "C46") (pin "1") (pinfunction "1_1") (pintype "bidirectional"))
      (node (ref "C52") (pin "1") (pinfunction "1_1") (pintype "bidirectional"))
      (node (ref "R17") (pin "2") (pinfunction "2_2") (pintype "bidirectional"))
    )
    (net (code "8") (name "/AOUT_R") (class "Default")
      (node (ref "C47") (pin "2") (pinfunction "2_2") (pintype "bidirectional"))
      (node (ref "C53") (pin "1") (pinfunction "1_1") (pintype "bidirectional"))
      (node (ref "R16") (pin "2") (pinfunction "2_2") (pintype "bidirectional"))
    )
    (net (code "9") (name "/GSM_PWR_EN") (class "Default")
      (node (ref "N1") (pin "3") (pinfunction "PA7/ADC7_3") (pintype "bidirectional"))
      (node (ref "R3") (pin "1") (pinfunction "1_1") (pintype "bidirectional"))
      (node (ref "U7") (pin "2") (pinfunction "A_2") (pintype "bidirectional"))
    )
    (net (code "10") (name "/GSM_PWR_KEY") (class "Default")
      (node (ref "N1") (pin "9") (pinfunction "PA1/ADC1_9") (pintype "bidirectional"))
      (node (ref "U6") (pin "P$13") (pinfunction "B7_P$13") (pintype "bidirectional"))
    )
    (net (code "11") (name "/GSM_RING") (class "Default")
      (node (ref "N1") (pin "8") (pinfunction "PA2/ADC2_8") (pintype "bidirectional"))
      (node (ref "U6") (pin "P$14") (pinfunction "B6_P$14") (pintype "bidirectional"))
    )
    (net (code "12") (name "/GSM_RXD") (class "Default")
      (node (ref "N1") (pin "18") (pinfunction "PD3/TXD1_18") (pintype "bidirectional"))
      (node (ref "U6") (pin "P$16") (pinfunction "B4_P$16") (pintype "bidirectional"))
    )
    (net (code "13") (name "/GSM_STATUS") (class "Default")
      (node (ref "N1") (pin "10") (pinfunction "PA0/ADC0_10") (pintype "bidirectional"))
      (node (ref "U6") (pin "P$12") (pinfunction "B8_P$12") (pintype "bidirectional"))
    )
    (net (code "14") (name "/GSM_TXD") (class "Default")
      (node (ref "N1") (pin "17") (pinfunction "PD2/RXD1_17") (pintype "bidirectional"))
      (node (ref "U6") (pin "P$15") (pinfunction "B5_P$15") (pintype "bidirectional"))
    )
    (net (code "15") (name "/I2C_SCL") (class "Default")
      (node (ref "J3") (pin "CLK") (pinfunction "CLK_CLK") (pintype "bidirectional"))
      (node (ref "N1") (pin "23") (pinfunction "PC0/SCL_23") (pintype "bidirectional"))
      (node (ref "R10") (pin "1") (pinfunction "1_1") (pintype "bidirectional"))
      (node (ref "U12") (pin "32") (pinfunction "SCL_32") (pintype "bidirectional"))
      (node (ref "U3") (pin "19") (pinfunction "SCL_19") (pintype "bidirectional"))
      (node (ref "U4") (pin "19") (pinfunction "SCL_19") (pintype "bidirectional"))
      (node (ref "U5") (pin "19") (pinfunction "SCL_19") (pintype "bidirectional"))
    )
    (net (code "16") (name "/I2C_SDA") (class "Default")
      (node (ref "J3") (pin "DATA") (pinfunction "DATA_DATA") (pintype "bidirectional"))
      (node (ref "N1") (pin "24") (pinfunction "PC1/SDA_24") (pintype "bidirectional"))
      (node (ref "R20") (pin "1") (pinfunction "1_1") (pintype "bidirectional"))
      (node (ref "U12") (pin "31") (pinfunction "SDA_31") (pintype "bidirectional"))
      (node (ref "U3") (pin "20") (pinfunction "SDA_20") (pintype "bidirectional"))
      (node (ref "U4") (pin "20") (pinfunction "SDA_20") (pintype "bidirectional"))
      (node (ref "U5") (pin "20") (pinfunction "SDA_20") (pintype "bidirectional"))
    )
    (net (code "17") (name "/MICROSD_CS") (class "Default")
      (node (ref "J4") (pin "DAT3/CS") (pinfunction "DAT3/CS_DAT3/CS") (pintype "bidirectional"))
      (node (ref "N1") (pin "21") (pinfunction "PD6_21") (pintype "bidirectional"))
    )
    (net (code "18") (name "/SPI_MISO") (class "Default")
      (node (ref "J4") (pin "DAT0/DO") (pinfunction "DAT0/DO_DAT0/DO") (pintype "bidirectional"))
      (node (ref "N1") (pin "32") (pinfunction "MISO_32") (pintype "bidirectional"))
    )
    (net (code "19") (name "/SPI_MOSI") (class "Default")
      (node (ref "J4") (pin "CMD/DI") (pinfunction "CMD/DI_CMD/DI") (pintype "bidirectional"))
      (node (ref "N1") (pin "31") (pinfunction "MOSI_31") (pintype "bidirectional"))
      (node (ref "U12") (pin "34") (pinfunction "SDI_34") (pintype "bidirectional"))
    )
    (net (code "20") (name "/SPI_SCK") (class "Default")
      (node (ref "J4") (pin "CLK/SCK") (pinfunction "CLK/SCK_CLK/SCK") (pintype "bidirectional"))
      (node (ref "N1") (pin "33") (pinfunction "SCK_33") (pintype "bidirectional"))
      (node (ref "U12") (pin "36") (pinfunction "SCKR_36") (pintype "bidirectional"))
    )
    (net (code "21") (name "/STA013_BIT_EN") (class "Default")
      (node (ref "N1") (pin "27") (pinfunction "PC4_27") (pintype "bidirectional"))
      (node (ref "U12") (pin "38") (pinfunction "BIT_EN_38") (pintype "bidirectional"))
    )
    (net (code "22") (name "/STA013_DREQ") (class "Default")
      (node (ref "N1") (pin "25") (pinfunction "PC2_25") (pintype "bidirectional"))
      (node (ref "U12") (pin "27") (pinfunction "OUT_CLK/DATA_REC_27") (pintype "bidirectional"))
    )
    (net (code "23") (name "/STA013_LRCKT") (class "Default")
      (node (ref "U12") (pin "2") (pinfunction "LRCKT_2") (pintype "bidirectional"))
      (node (ref "U13") (pin "P$3") (pinfunction "LRCK_P$3") (pintype "bidirectional"))
    )
    (net (code "24") (name "/STA013_OCLK") (class "Default")
      (node (ref "U12") (pin "3") (pinfunction "OCLK_3") (pintype "bidirectional"))
      (node (ref "U13") (pin "P$4") (pinfunction "MCLK_P$4") (pintype "bidirectional"))
    )
    (net (code "25") (name "/STA013_SCKT") (class "Default")
      (node (ref "U12") (pin "44") (pinfunction "SCKT_44") (pintype "bidirectional"))
      (node (ref "U13") (pin "P$2") (pinfunction "DEM/SCLK_P$2") (pintype "bidirectional"))
    )
    (net (code "26") (name "/STA013_SDO") (class "Default")
      (node (ref "U12") (pin "42") (pinfunction "SDO_42") (pintype "bidirectional"))
      (node (ref "U13") (pin "P$1") (pinfunction "SDATA_P$1") (pintype "bidirectional"))
    )
    (net (code "27") (name "/VBAT") (class "Default")
      (node (ref "BAT[+-]") (pin "1") (pinfunction "1_1") (pintype "bidirectional"))
      (node (ref "S1") (pin "2") (pinfunction "1_2") (pintype "bidirectional"))
    )
    (net (code "28") (name "/VIBRATOR_EN") (class "Default")
      (node (ref "N1") (pin "14") (pinfunction "PB3_14") (pintype "bidirectional"))
      (node (ref "R23") (pin "1") (pinfunction "1_1") (pintype "bidirectional"))
      (node (ref "U16") (pin "2") (pinfunction "A_2") (pintype "bidirectional"))
    )
    (net (code "29") (name "/~{STA013_RST}") (class "Default")
      (node (ref "N1") (pin "26") (pinfunction "PC3_26") (pintype "bidirectional"))
      (node (ref "R14") (pin "1") (pinfunction "1_1") (pintype "bidirectional"))
      (node (ref "U12") (pin "25") (pinfunction "~{RESET}_25") (pintype "bidirectional"))
    )
    (net (code "30") (name "GND") (class "Default")
      (node (ref "B1") (pin "2") (pinfunction "2_2") (pintype "bidirectional"))
      (node (ref "B10") (pin "2") (pinfunction "2_2") (pintype "bidirectional"))
      (node (ref "B11") (pin "2") (pinfunction "2_2") (pintype "bidirectional"))
      (node (ref "B12") (pin "2") (pinfunction "2_2") (pintype "bidirectional"))
      (node (ref "B13") (pin "5") (pinfunction "COMMON_5") (pintype "bidirectional"))
      (node (ref "B13") (pin "GND1") (pinfunction "GND1_GND1") (pintype "bidirectional"))
      (node (ref "B13") (pin "GND2") (pinfunction "GND2_GND2") (pintype "bidirectional"))
      (node (ref "B14") (pin "1") (pinfunction "1_1") (pintype "bidirectional"))
      (node (ref "B15") (pin "2") (pinfunction "2_2") (pintype "bidirectional"))
      (node (ref "B16") (pin "1") (pinfunction "1_1") (pintype "bidirectional"))
      (node (ref "B17") (pin "2") (pinfunction "2_2") (pintype "bidirectional"))
      (node (ref "B2") (pin "2") (pinfunction "2_2") (pintype "bidirectional"))
      (node (ref "B3") (pin "2") (pinfunction "2_2") (pintype "bidirectional"))
      (node (ref "B4") (pin "2") (pinfunction "2_2") (pintype "bidirectional"))
      (node (ref "B5") (pin "2") (pinfunction "2_2") (pintype "bidirectional"))
      (node (ref "B6") (pin "2") (pinfunction "2_2") (pintype "bidirectional"))
      (node (ref "B7") (pin "2") (pinfunction "2_2") (pintype "bidirectional"))
      (node (ref "B8") (pin "2") (pinfunction "2_2") (pintype "bidirectional"))
      (node (ref "B9") (pin "2") (pinfunction "2_2") (pintype "bidirectional"))
      (node (ref "BAT[+-]") (pin "2") (pinfunction "2_2") (pintype "bidirectional"))
      (node (ref "C1") (pin "1") (pinfunction "1_1") (pintype "bidirectional"))
      (node (ref "C10") (pin "2") (pinfunction "2_2") (pintype "bidirectional"))
      (node (ref "C13") (pin "1") (pinfunction "1_1") (pintype "bidirectional"))
      (node (ref "C14") (pin "1") (pinfunction "1_1") (pintype "bidirectional"))
      (node (ref "C15") (pin "1") (pinfunction "1_1") (pintype "bidirectional"))
      (node (ref "C16") (pin "1") (pinfunction "1_1") (pintype "bidirectional"))
      (node (ref "C19") (pin "1") (pinfunction "1_1") (pintype "bidirectional"))
      (node (ref "C2") (pin "1") (pinfunction "1_1") (pintype "bidirectional"))
      (node (ref "C20") (pin "1") (pinfunction "1_1") (pintype "bidirectional"))
      (node (ref "C21") (pin "1") (pinfunction "1_1") (pintype "bidirectional"))
      (node (ref "C22") (pin "1") (pinfunction "1_1") (pintype "bidirectional"))
      (node (ref "C23") (pin "1") (pinfunction "1_1") (pintype "bidirectional"))
      (node (ref "C24") (pin "1") (pinfunction "1_1") (pintype "bidirectional"))
      (node (ref "C25") (pin "2") (pinfunction "2_2") (pintype "bidirectional"))
      (node (ref "C26") (pin "1") (pinfunction "1_1") (pintype "bidirectional"))
      (node (ref "C27") (pin "1") (pinfunction "1_1") (pintype "bidirectional"))
      (node (ref "C28") (pin "1") (pinfunction "1_1") (pintype "bidirectional"))
      (node (ref "C29") (pin "2") (pinfunction "2_2") (pintype "bidirectional"))
      (node (ref "C3") (pin "2") (pinfunction "2_2") (pintype "bidirectional"))
      (node (ref "C30") (pin "2") (pinfunction "2_2") (pintype "bidirectional"))
      (node (ref "C31") (pin "2") (pinfunction "2_2") (pintype "bidirectional"))
      (node (ref "C32") (pin "2") (pinfunction "2_2") (pintype "bidirectional"))
      (node (ref "C33") (pin "1") (pinfunction "1_1") (pintype "bidirectional"))
      (node (ref "C34") (pin "1") (pinfunction "1_1") (pintype "bidirectional"))
      (node (ref "C35") (pin "1") (pinfunction "1_1") (pintype "bidirectional"))
      (node (ref "C36") (pin "1") (pinfunction "1_1") (pintype "bidirectional"))
      (node (ref "C37") (pin "1") (pinfunction "1_1") (pintype "bidirectional"))
      (node (ref "C38") (pin "1") (pinfunction "1_1") (pintype "bidirectional"))
      (node (ref "C4") (pin "2") (pinfunction "2_2") (pintype "bidirectional"))
      (node (ref "C40") (pin "1") (pinfunction "1_1") (pintype "bidirectional"))
      (node (ref "C41") (pin "1") (pinfunction "1_1") (pintype "bidirectional"))
      (node (ref "C42") (pin "1") (pinfunction "1_1") (pintype "bidirectional"))
      (node (ref "C45") (pin "2") (pinfunction "2_2") (pintype "bidirectional"))
      (node (ref "C46") (pin "2") (pinfunction "2_2") (pintype "bidirectional"))
      (node (ref "C47") (pin "1") (pinfunction "1_1") (pintype "bidirectional"))
      (node (ref "C48") (pin "1") (pinfunction "1_1") (pintype "bidirectional"))
      (node (ref "C5") (pin "2") (pinfunction "2_2") (pintype "bidirectional"))
      (node (ref "C51") (pin "1") (pinfunction "1_1") (pintype "bidirectional"))
      (node (ref "C54") (pin "1") (pinfunction "1_1") (pintype "bidirectional"))
      (node (ref "C55") (pin "1") (pinfunction "1_1") (pintype "bidirectional"))
      (node (ref "C56") (pin "2") (pinfunction "2_2") (pintype "bidirectional"))
      (node (ref "C6") (pin "2") (pinfunction "2_2") (pintype "bidirectional"))
      (node (ref "C7") (pin "1") (pinfunction "1_1") (pintype "bidirectional"))
      (node (ref "C8") (pin "1") (pinfunction "1_1") (pintype "bidirectional"))
      (node (ref "C9") (pin "1") (pinfunction "1_1") (pintype "bidirectional"))
      (node (ref "D1") (pin "2") (pinfunction "2_2") (pintype "bidirectional"))
      (node (ref "D2") (pin "2") (pinfunction "2_2") (pintype "bidirectional"))
      (node (ref "J3") (pin "GND") (pinfunction "GND_GND") (pintype "bidirectional"))
      (node (ref "J4") (pin "GND1") (pinfunction "GND_1_GND1") (pintype "bidirectional"))
      (node (ref "J4") (pin "GND2") (pinfunction "GND_2_GND2") (pintype "bidirectional"))
      (node (ref "J4") (pin "GND3") (pinfunction "GND_3_GND3") (pintype "bidirectional"))
      (node (ref "J4") (pin "GND4") (pinfunction "GND_4_GND4") (pintype "bidirectional"))
      (node (ref "J4") (pin "VSS") (pinfunction "GND_VSS") (pintype "bidirectional"))
      (node (ref "J5") (pin "1") (pinfunction "SLEEVE_1") (pintype "bidirectional"))
      (node (ref "J6") (pin "P$1") (pinfunction "GND_P$1") (pintype "bidirectional"))
      (node (ref "J6") (pin "P$2") (pinfunction "GND_P$2") (pintype "bidirectional"))
      (node (ref "M1") (pin "1") (pinfunction "-_1") (pintype "bidirectional"))
      (node (ref "N1") (pin "1") (pinfunction "GND_1") (pintype "bidirectional"))
      (node (ref "N1") (pin "15") (pinfunction "GND_15") (pintype "bidirectional"))
      (node (ref "N1") (pin "35") (pinfunction "GND_35") (pintype "bidirectional"))
      (node (ref "R1") (pin "1") (pinfunction "1_1") (pintype "bidirectional"))
      (node (ref "R12") (pin "2") (pinfunction "2_2") (pintype "bidirectional"))
      (node (ref "R18") (pin "2") (pinfunction "2_2") (pintype "bidirectional"))
      (node (ref "R19") (pin "1") (pinfunction "1_1") (pintype "bidirectional"))
      (node (ref "R2") (pin "1") (pinfunction "1_1") (pintype "bidirectional"))
      (node (ref "R23") (pin "2") (pinfunction "2_2") (pintype "bidirectional"))
      (node (ref "R3") (pin "2") (pinfunction "2_2") (pintype "bidirectional"))
      (node (ref "R4") (pin "2") (pinfunction "2_2") (pintype "bidirectional"))
      (node (ref "R6") (pin "2") (pinfunction "2_2") (pintype "bidirectional"))
      (node (ref "U1") (pin "P$17") (pinfunction "GND_P$17") (pintype "bidirectional"))
      (node (ref "U1") (pin "P$18") (pinfunction "GND_P$18") (pintype "bidirectional"))
      (node (ref "U1") (pin "P$2") (pinfunction "GND_P$2") (pintype "bidirectional"))
      (node (ref "U1") (pin "P$29") (pinfunction "GND_P$29") (pintype "bidirectional"))
      (node (ref "U1") (pin "P$39") (pinfunction "GND_P$39") (pintype "bidirectional"))
      (node (ref "U1") (pin "P$45") (pinfunction "GND_P$45") (pintype "bidirectional"))
      (node (ref "U1") (pin "P$46") (pinfunction "GND_P$46") (pintype "bidirectional"))
      (node (ref "U1") (pin "P$54") (pinfunction "GND_P$54") (pintype "bidirectional"))
      (node (ref "U1") (pin "P$58") (pinfunction "GND_P$58") (pintype "bidirectional"))
      (node (ref "U1") (pin "P$59") (pinfunction "GND_P$59") (pintype "bidirectional"))
      (node (ref "U1") (pin "P$61") (pinfunction "GND_P$61") (pintype "bidirectional"))
      (node (ref "U1") (pin "P$62") (pinfunction "GND_P$62") (pintype "bidirectional"))
      (node (ref "U1") (pin "P$63") (pinfunction "GND_P$63") (pintype "bidirectional"))
      (node (ref "U1") (pin "P$64") (pinfunction "GND_P$64") (pintype "bidirectional"))
      (node (ref "U1") (pin "P$65") (pinfunction "GND_P$65") (pintype "bidirectional"))
      (node (ref "U10") (pin "2") (pinfunction "GND_2") (pintype "bidirectional"))
      (node (ref "U11") (pin "6") (pinfunction "PGND_6") (pintype "bidirectional"))
      (node (ref "U11") (pin "7") (pinfunction "SGND_7") (pintype "bidirectional"))
      (node (ref "U12") (pin "19") (pinfunction "VSS_4_19") (pintype "bidirectional"))
      (node (ref "U12") (pin "24") (pinfunction "SCANEN_24") (pintype "bidirectional"))
      (node (ref "U12") (pin "26") (pinfunction "VSS_5_26") (pintype "bidirectional"))
      (node (ref "U12") (pin "30") (pinfunction "VSS_1_30") (pintype "bidirectional"))
      (node (ref "U12") (pin "5") (pinfunction "VSS_2_5") (pintype "bidirectional"))
      (node (ref "U12") (pin "7") (pinfunction "VSS_3_7") (pintype "bidirectional"))
      (node (ref "U13") (pin "P$6") (pinfunction "AGND_P$6") (pintype "bidirectional"))
      (node (ref "U14") (pin "5") (pinfunction "GND_5") (pintype "bidirectional"))
      (node (ref "U15") (pin "2") (pinfunction "GND_2") (pintype "bidirectional"))
      (node (ref "U16") (pin "1") (pinfunction "~{OE}_1") (pintype "bidirectional"))
      (node (ref "U16") (pin "3") (pinfunction "GND_3") (pintype "bidirectional"))
      (node (ref "U2") (pin "P$3") (pinfunction "GND_P$3") (pintype "bidirectional"))
      (node (ref "U2") (pin "P$6") (pinfunction "GND_P$6") (pintype "bidirectional"))
      (node (ref "U3") (pin "17") (pinfunction "GND_17") (pintype "bidirectional"))
      (node (ref "U3") (pin "2") (pinfunction "A1_2") (pintype "bidirectional"))
      (node (ref "U3") (pin "3") (pinfunction "A0_3") (pintype "bidirectional"))
      (node (ref "U3") (pin "PAD") (pinfunction "PAD_PAD") (pintype "bidirectional"))
      (node (ref "U4") (pin "17") (pinfunction "GND_17") (pintype "bidirectional"))
      (node (ref "U4") (pin "2") (pinfunction "A1_2") (pintype "bidirectional"))
      (node (ref "U4") (pin "PAD") (pinfunction "PAD_PAD") (pintype "bidirectional"))
      (node (ref "U5") (pin "17") (pinfunction "GND_17") (pintype "bidirectional"))
      (node (ref "U5") (pin "3") (pinfunction "A0_3") (pintype "bidirectional"))
      (node (ref "U5") (pin "PAD") (pinfunction "PAD_PAD") (pintype "bidirectional"))
      (node (ref "U6") (pin "P$11") (pinfunction "GND_P$11") (pintype "bidirectional"))
      (node (ref "U7") (pin "1") (pinfunction "~{OE}_1") (pintype "bidirectional"))
      (node (ref "U7") (pin "3") (pinfunction "GND_3") (pintype "bidirectional"))
      (node (ref "U8") (pin "C5") (pinfunction "GND_C5") (pintype "bidirectional"))
      (node (ref "U8") (pin "GND@L") (pinfunction "GND_GND@L") (pintype "bidirectional"))
      (node (ref "U8") (pin "GND@R") (pinfunction "GND_GND@R") (pintype "bidirectional"))
      (node (ref "U9") (pin "P$2") (pinfunction "COMMON_P$2") (pintype "bidirectional"))
      (node (ref "X2") (pin "2") (pinfunction "GND0_2") (pintype "bidirectional"))
      (node (ref "X2") (pin "4") (pinfunction "GND1_4") (pintype "bidirectional"))
    )
    (net (code "31") (name "Net-(B13-A)") (class "Default")
      (node (ref "B13") (pin "1") (pinfunction "A_1") (pintype "bidirectional"))
      (node (ref "U3") (pin "12") (pinfunction "GP3_12") (pintype "bidirectional"))
    )
    (net (code "32") (name "Net-(B13-B)") (class "Default")
      (node (ref "B13") (pin "4") (pinfunction "B_4") (pintype "bidirectional"))
      (node (ref "U3") (pin "10") (pinfunction "GP1_10") (pintype "bidirectional"))
    )
    (net (code "33") (name "Net-(B13-C)") (class "Default")
      (node (ref "B13") (pin "3") (pinfunction "C_3") (pintype "bidirectional"))
      (node (ref "U3") (pin "14") (pinfunction "GP5_14") (pintype "bidirectional"))
    )
    (net (code "34") (name "Net-(B13-CENTER)") (class "Default")
      (node (ref "B13") (pin "2") (pinfunction "CENTER_2") (pintype "bidirectional"))
      (node (ref "U3") (pin "13") (pinfunction "GP4_13") (pintype "bidirectional"))
    )
    (net (code "35") (name "Net-(B13-D)") (class "Default")
      (node (ref "B13") (pin "6") (pinfunction "D_6") (pintype "bidirectional"))
      (node (ref "U3") (pin "11") (pinfunction "GP2_11") (pintype "bidirectional"))
    )
    (net (code "36") (name "Net-(C41-Pad2)") (class "Default")
      (node (ref "C41") (pin "2") (pinfunction "2_2") (pintype "bidirectional"))
      (node (ref "R15") (pin "2") (pinfunction "2_2") (pintype "bidirectional"))
    )
    (net (code "37") (name "Net-(C43-Pad1)") (class "Default")
      (node (ref "C43") (pin "1") (pinfunction "1_1") (pintype "bidirectional"))
      (node (ref "R17") (pin "1") (pinfunction "1_1") (pintype "bidirectional"))
    )
    (net (code "38") (name "Net-(C44-Pad1)") (class "Default")
      (node (ref "C44") (pin "1") (pinfunction "1_1") (pintype "bidirectional"))
      (node (ref "R16") (pin "1") (pinfunction "1_1") (pintype "bidirectional"))
    )
    (net (code "39") (name "Net-(D1-Pad1)") (class "Default")
      (node (ref "D1") (pin "1") (pinfunction "1_1") (pintype "bidirectional"))
      (node (ref "R21") (pin "2") (pinfunction "2_2") (pintype "bidirectional"))
    )
    (net (code "40") (name "Net-(D2-Pad1)") (class "Default")
      (node (ref "D2") (pin "1") (pinfunction "1_1") (pintype "bidirectional"))
      (node (ref "R24") (pin "2") (pinfunction "2_2") (pintype "bidirectional"))
    )
    (net (code "41") (name "Net-(J5-RING)") (class "Default")
      (node (ref "C50") (pin "1") (pinfunction "1_1") (pintype "bidirectional"))
      (node (ref "J5") (pin "3") (pinfunction "RING_3") (pintype "bidirectional"))
    )
    (net (code "42") (name "Net-(J5-TIP)") (class "Default")
      (node (ref "C49") (pin "1") (pinfunction "1_1") (pintype "bidirectional"))
      (node (ref "J5") (pin "2") (pinfunction "TIP_2") (pintype "bidirectional"))
    )
    (net (code "43") (name "Net-(J6-SIG)") (class "Default")
      (node (ref "J6") (pin "P$3") (pinfunction "SIG_P$3") (pintype "bidirectional"))
      (node (ref "U1") (pin "P$60") (pinfunction "RF_ANT_P$60") (pintype "bidirectional"))
    )
    (net (code "44") (name "Net-(M1-+)") (class "Default")
      (node (ref "C55") (pin "2") (pinfunction "2_2") (pintype "bidirectional"))
      (node (ref "M1") (pin "2") (pinfunction "+_2") (pintype "bidirectional"))
      (node (ref "U15") (pin "5") (pinfunction "VOUT_5") (pintype "bidirectional"))
    )
    (net (code "45") (name "Net-(N1-PD4)") (class "Default")
      (node (ref "N1") (pin "19") (pinfunction "PD4_19") (pintype "bidirectional"))
      (node (ref "R24") (pin "1") (pinfunction "1_1") (pintype "bidirectional"))
    )
    (net (code "46") (name "Net-(N1-PD5)") (class "Default")
      (node (ref "N1") (pin "20") (pinfunction "PD5_20") (pintype "bidirectional"))
      (node (ref "R21") (pin "1") (pinfunction "1_1") (pintype "bidirectional"))
    )
    (net (code "47") (name "Net-(S1-2)") (class "Default")
      (node (ref "C25") (pin "1") (pinfunction "1_1") (pintype "bidirectional"))
      (node (ref "L1") (pin "1") (pinfunction "1_1") (pintype "bidirectional"))
      (node (ref "S1") (pin "3") (pinfunction "2_3") (pintype "bidirectional"))
      (node (ref "U11") (pin "1") (pinfunction "EN_1") (pintype "bidirectional"))
      (node (ref "U11") (pin "8") (pinfunction "VIN_8") (pintype "bidirectional"))
    )
    (net (code "48") (name "Net-(U1-MIC_N)") (class "Default")
      (node (ref "C17") (pin "1") (pinfunction "1_1") (pintype "bidirectional"))
      (node (ref "C18") (pin "1") (pinfunction "1_1") (pintype "bidirectional"))
      (node (ref "C19") (pin "2") (pinfunction "2_2") (pintype "bidirectional"))
      (node (ref "C22") (pin "2") (pinfunction "2_2") (pintype "bidirectional"))
      (node (ref "J2") (pin "-") (pinfunction "-_-") (pintype "bidirectional"))
      (node (ref "U1") (pin "P$20") (pinfunction "MIC_N_P$20") (pintype "bidirectional"))
    )
    (net (code "49") (name "Net-(U1-MIC_P)") (class "Default")
      (node (ref "C17") (pin "2") (pinfunction "2_2") (pintype "bidirectional"))
      (node (ref "C18") (pin "2") (pinfunction "2_2") (pintype "bidirectional"))
      (node (ref "C20") (pin "2") (pinfunction "2_2") (pintype "bidirectional"))
      (node (ref "C21") (pin "2") (pinfunction "2_2") (pintype "bidirectional"))
      (node (ref "J2") (pin "+") (pinfunction "+_+") (pintype "bidirectional"))
      (node (ref "U1") (pin "P$19") (pinfunction "MIC_P_P$19") (pintype "bidirectional"))
    )
    (net (code "50") (name "Net-(U1-PWRKEY)") (class "Default")
      (node (ref "U1") (pin "P$1") (pinfunction "PWRKEY_P$1") (pintype "bidirectional"))
      (node (ref "U6") (pin "P$8") (pinfunction "A7_P$8") (pintype "bidirectional"))
    )
    (net (code "51") (name "Net-(U1-RI)") (class "Default")
      (node (ref "U1") (pin "P$4") (pinfunction "RI_P$4") (pintype "bidirectional"))
      (node (ref "U6") (pin "P$7") (pinfunction "A6_P$7") (pintype "bidirectional"))
    )
    (net (code "52") (name "Net-(U1-RXD)") (class "Default")
      (node (ref "U1") (pin "P$10") (pinfunction "RXD_P$10") (pintype "bidirectional"))
      (node (ref "U6") (pin "P$5") (pinfunction "A4_P$5") (pintype "bidirectional"))
    )
    (net (code "53") (name "Net-(U1-SPK_N)") (class "Default")
      (node (ref "C11") (pin "2") (pinfunction "2_2") (pintype "bidirectional"))
      (node (ref "C12") (pin "2") (pinfunction "2_2") (pintype "bidirectional"))
      (node (ref "C14") (pin "2") (pinfunction "2_2") (pintype "bidirectional"))
      (node (ref "C15") (pin "2") (pinfunction "2_2") (pintype "bidirectional"))
      (node (ref "J1") (pin "-") (pinfunction "-_-") (pintype "bidirectional"))
      (node (ref "U1") (pin "P$22") (pinfunction "SPK_N_P$22") (pintype "bidirectional"))
    )
    (net (code "54") (name "Net-(U1-SPK_P)") (class "Default")
      (node (ref "C11") (pin "1") (pinfunction "1_1") (pintype "bidirectional"))
      (node (ref "C12") (pin "1") (pinfunction "1_1") (pintype "bidirectional"))
      (node (ref "C13") (pin "2") (pinfunction "2_2") (pintype "bidirectional"))
      (node (ref "C16") (pin "2") (pinfunction "2_2") (pintype "bidirectional"))
      (node (ref "J1") (pin "+") (pinfunction "+_+") (pintype "bidirectional"))
      (node (ref "U1") (pin "P$21") (pinfunction "SPK_P_P$21") (pintype "bidirectional"))
    )
    (net (code "55") (name "Net-(U1-STATUS)") (class "Default")
      (node (ref "U1") (pin "P$66") (pinfunction "STATUS_P$66") (pintype "bidirectional"))
      (node (ref "U6") (pin "P$9") (pinfunction "A8_P$9") (pintype "bidirectional"))
    )
    (net (code "56") (name "Net-(U1-TXD)") (class "Default")
      (node (ref "U1") (pin "P$9") (pinfunction "TXD_P$9") (pintype "bidirectional"))
      (node (ref "U6") (pin "P$6") (pinfunction "A5_P$6") (pintype "bidirectional"))
    )
    (net (code "57") (name "Net-(U1-USIM_CLK)") (class "Default")
      (node (ref "C8") (pin "2") (pinfunction "2_2") (pintype "bidirectional"))
      (node (ref "R8") (pin "2") (pinfunction "2_2") (pintype "bidirectional"))
      (node (ref "U1") (pin "P$32") (pinfunction "USIM_CLK_P$32") (pintype "bidirectional"))
    )
    (net (code "58") (name "Net-(U1-USIM_DATA)") (class "Default")
      (node (ref "C7") (pin "2") (pinfunction "2_2") (pintype "bidirectional"))
      (node (ref "R9") (pin "2") (pinfunction "2_2") (pintype "bidirectional"))
      (node (ref "U1") (pin "P$31") (pinfunction "USIM_DATA_P$31") (pintype "bidirectional"))
    )
    (net (code "59") (name "Net-(U1-USIM_RST)") (class "Default")
      (node (ref "C9") (pin "2") (pinfunction "2_2") (pintype "bidirectional"))
      (node (ref "R7") (pin "2") (pinfunction "2_2") (pintype "bidirectional"))
      (node (ref "U1") (pin "P$33") (pinfunction "USIM_RST_P$33") (pintype "bidirectional"))
    )
    (net (code "60") (name "Net-(U1-USIM_VDD)") (class "Default")
      (node (ref "C10") (pin "1") (pinfunction "1_1") (pintype "bidirectional"))
      (node (ref "U1") (pin "P$30") (pinfunction "USIM_VDD_P$30") (pintype "bidirectional"))
      (node (ref "U8") (pin "C1") (pinfunction "VCC_C1") (pintype "bidirectional"))
      (node (ref "U9") (pin "P$6") (pinfunction "X5_P$6") (pintype "bidirectional"))
    )
    (net (code "61") (name "Net-(U1-VDD_EXT)") (class "Default")
      (node (ref "C1") (pin "2") (pinfunction "2_2") (pintype "bidirectional"))
      (node (ref "U1") (pin "P$15") (pinfunction "VDD_EXT_P$15") (pintype "bidirectional"))
      (node (ref "U6") (pin "P$10") (pinfunction "OE_P$10") (pintype "bidirectional"))
      (node (ref "U6") (pin "P$2") (pinfunction "VCCA_P$2") (pintype "bidirectional"))
    )
    (net (code "62") (name "Net-(U2-ADJ)") (class "Default")
      (node (ref "R4") (pin "1") (pinfunction "1_1") (pintype "bidirectional"))
      (node (ref "R5") (pin "2") (pinfunction "2_2") (pintype "bidirectional"))
      (node (ref "U2") (pin "P$5") (pinfunction "ADJ_P$5") (pintype "bidirectional"))
    )
    (net (code "63") (name "Net-(U2-EN)") (class "Default")
      (node (ref "U2") (pin "P$1") (pinfunction "EN_P$1") (pintype "bidirectional"))
      (node (ref "U7") (pin "4") (pinfunction "Y_4") (pintype "bidirectional"))
    )
    (net (code "64") (name "Net-(U3-GP0)") (class "Default")
      (node (ref "B16") (pin "2") (pinfunction "2_2") (pintype "bidirectional"))
      (node (ref "U3") (pin "9") (pinfunction "GP0_9") (pintype "bidirectional"))
    )
    (net (code "65") (name "Net-(U3-GP6)") (class "Default")
      (node (ref "B14") (pin "2") (pinfunction "2_2") (pintype "bidirectional"))
      (node (ref "U3") (pin "15") (pinfunction "GP6_15") (pintype "bidirectional"))
    )
    (net (code "66") (name "Net-(U3-GP7)") (class "Default")
      (node (ref "B17") (pin "1") (pinfunction "1_1") (pintype "bidirectional"))
      (node (ref "U3") (pin "16") (pinfunction "GP7_16") (pintype "bidirectional"))
    )
    (net (code "67") (name "Net-(U4-GP0)") (class "Default")
      (node (ref "B15") (pin "1") (pinfunction "1_1") (pintype "bidirectional"))
      (node (ref "U4") (pin "9") (pinfunction "GP0_9") (pintype "bidirectional"))
    )
    (net (code "68") (name "Net-(U4-GP1)") (class "Default")
      (node (ref "B9") (pin "1") (pinfunction "1_1") (pintype "bidirectional"))
      (node (ref "U4") (pin "10") (pinfunction "GP1_10") (pintype "bidirectional"))
    )
    (net (code "69") (name "Net-(U4-GP2)") (class "Default")
      (node (ref "B5") (pin "1") (pinfunction "1_1") (pintype "bidirectional"))
      (node (ref "U4") (pin "11") (pinfunction "GP2_11") (pintype "bidirectional"))
    )
    (net (code "70") (name "Net-(U4-GP3)") (class "Default")
      (node (ref "B1") (pin "1") (pinfunction "1_1") (pintype "bidirectional"))
      (node (ref "U4") (pin "12") (pinfunction "GP3_12") (pintype "bidirectional"))
    )
    (net (code "71") (name "Net-(U4-GP4)") (class "Default")
      (node (ref "B10") (pin "1") (pinfunction "1_1") (pintype "bidirectional"))
      (node (ref "U4") (pin "13") (pinfunction "GP4_13") (pintype "bidirectional"))
    )
    (net (code "72") (name "Net-(U4-GP5)") (class "Default")
      (node (ref "B6") (pin "1") (pinfunction "1_1") (pintype "bidirectional"))
      (node (ref "U4") (pin "14") (pinfunction "GP5_14") (pintype "bidirectional"))
    )
    (net (code "73") (name "Net-(U4-GP6)") (class "Default")
      (node (ref "B2") (pin "1") (pinfunction "1_1") (pintype "bidirectional"))
      (node (ref "U4") (pin "15") (pinfunction "GP6_15") (pintype "bidirectional"))
    )
    (net (code "74") (name "Net-(U4-GP7)") (class "Default")
      (node (ref "B11") (pin "1") (pinfunction "1_1") (pintype "bidirectional"))
      (node (ref "U4") (pin "16") (pinfunction "GP7_16") (pintype "bidirectional"))
    )
    (net (code "75") (name "Net-(U5-GP0)") (class "Default")
      (node (ref "B3") (pin "1") (pinfunction "1_1") (pintype "bidirectional"))
      (node (ref "U5") (pin "9") (pinfunction "GP0_9") (pintype "bidirectional"))
    )
    (net (code "76") (name "Net-(U5-GP1)") (class "Default")
      (node (ref "B4") (pin "1") (pinfunction "1_1") (pintype "bidirectional"))
      (node (ref "U5") (pin "10") (pinfunction "GP1_10") (pintype "bidirectional"))
    )
    (net (code "77") (name "Net-(U5-GP2)") (class "Default")
      (node (ref "B7") (pin "1") (pinfunction "1_1") (pintype "bidirectional"))
      (node (ref "U5") (pin "11") (pinfunction "GP2_11") (pintype "bidirectional"))
    )
    (net (code "78") (name "Net-(U5-GP3)") (class "Default")
      (node (ref "B8") (pin "1") (pinfunction "1_1") (pintype "bidirectional"))
      (node (ref "U5") (pin "12") (pinfunction "GP3_12") (pintype "bidirectional"))
    )
    (net (code "79") (name "Net-(U5-GP4)") (class "Default")
      (node (ref "B12") (pin "1") (pinfunction "1_1") (pintype "bidirectional"))
      (node (ref "U5") (pin "13") (pinfunction "GP4_13") (pintype "bidirectional"))
    )
    (net (code "80") (name "Net-(U6-A1)") (class "Default")
      (node (ref "R2") (pin "2") (pinfunction "2_2") (pintype "bidirectional"))
      (node (ref "U6") (pin "P$1") (pinfunction "A1_P$1") (pintype "bidirectional"))
      (node (ref "U6") (pin "P$3") (pinfunction "A2_P$3") (pintype "bidirectional"))
      (node (ref "U6") (pin "P$4") (pinfunction "A3_P$4") (pintype "bidirectional"))
    )
    (net (code "81") (name "Net-(U6-B1)") (class "Default")
      (node (ref "R1") (pin "2") (pinfunction "2_2") (pintype "bidirectional"))
      (node (ref "U6") (pin "P$17") (pinfunction "B3_P$17") (pintype "bidirectional"))
      (node (ref "U6") (pin "P$18") (pinfunction "B2_P$18") (pintype "bidirectional"))
      (node (ref "U6") (pin "P$20") (pinfunction "B1_P$20") (pintype "bidirectional"))
    )
    (net (code "82") (name "Net-(U8-CLK)") (class "Default")
      (node (ref "R8") (pin "1") (pinfunction "1_1") (pintype "bidirectional"))
      (node (ref "U8") (pin "C3") (pinfunction "CLK_C3") (pintype "bidirectional"))
      (node (ref "U9") (pin "P$4") (pinfunction "X3_P$4") (pintype "bidirectional"))
    )
    (net (code "83") (name "Net-(U8-IO)") (class "Default")
      (node (ref "R9") (pin "1") (pinfunction "1_1") (pintype "bidirectional"))
      (node (ref "U8") (pin "C7") (pinfunction "IO_C7") (pintype "bidirectional"))
      (node (ref "U9") (pin "P$5") (pinfunction "X4_P$5") (pintype "bidirectional"))
    )
    (net (code "84") (name "Net-(U8-RST)") (class "Default")
      (node (ref "R7") (pin "1") (pinfunction "1_1") (pintype "bidirectional"))
      (node (ref "U8") (pin "C2") (pinfunction "RST_C2") (pintype "bidirectional"))
      (node (ref "U9") (pin "P$3") (pinfunction "X2_P$3") (pintype "bidirectional"))
    )
    (net (code "85") (name "Net-(U11-SW)") (class "Default")
      (node (ref "L1") (pin "2") (pinfunction "2_2") (pintype "bidirectional"))
      (node (ref "U11") (pin "5") (pinfunction "SW_5") (pintype "bidirectional"))
    )
    (net (code "86") (name "Net-(U12-FILT)") (class "Default")
      (node (ref "C40") (pin "2") (pinfunction "2_2") (pintype "bidirectional"))
      (node (ref "R15") (pin "1") (pinfunction "1_1") (pintype "bidirectional"))
      (node (ref "U12") (pin "12") (pinfunction "FILT_12") (pintype "bidirectional"))
    )
    (net (code "87") (name "Net-(U12-PVDD)") (class "Default")
      (node (ref "C39") (pin "1") (pinfunction "1_1") (pintype "bidirectional"))
      (node (ref "R13") (pin "2") (pinfunction "2_2") (pintype "bidirectional"))
      (node (ref "U12") (pin "10") (pinfunction "PVDD_10") (pintype "bidirectional"))
    )
    (net (code "88") (name "Net-(U12-PVSS)") (class "Default")
      (node (ref "C39") (pin "2") (pinfunction "2_2") (pintype "bidirectional"))
      (node (ref "R12") (pin "1") (pinfunction "1_1") (pintype "bidirectional"))
      (node (ref "U12") (pin "11") (pinfunction "PVSS_11") (pintype "bidirectional"))
    )
    (net (code "89") (name "Net-(U12-XTI)") (class "Default")
      (node (ref "C34") (pin "2") (pinfunction "2_2") (pintype "bidirectional"))
      (node (ref "R11") (pin "1") (pinfunction "1_1") (pintype "bidirectional"))
      (node (ref "U12") (pin "15") (pinfunction "XTI_15") (pintype "bidirectional"))
      (node (ref "X2") (pin "1") (pinfunction "1_1") (pintype "bidirectional"))
    )
    (net (code "90") (name "Net-(U12-XTO)") (class "Default")
      (node (ref "C33") (pin "2") (pinfunction "2_2") (pintype "bidirectional"))
      (node (ref "R11") (pin "2") (pinfunction "2_2") (pintype "bidirectional"))
      (node (ref "U12") (pin "13") (pinfunction "XTO_13") (pintype "bidirectional"))
      (node (ref "X2") (pin "3") (pinfunction "2_3") (pintype "bidirectional"))
    )
    (net (code "91") (name "Net-(U13-AOUTL)") (class "Default")
      (node (ref "C43") (pin "2") (pinfunction "2_2") (pintype "bidirectional"))
      (node (ref "R18") (pin "1") (pinfunction "1_1") (pintype "bidirectional"))
      (node (ref "U13") (pin "P$8") (pinfunction "AOUTL_P$8") (pintype "bidirectional"))
    )
    (net (code "92") (name "Net-(U13-AOUTR)") (class "Default")
      (node (ref "C44") (pin "2") (pinfunction "2_2") (pintype "bidirectional"))
      (node (ref "R19") (pin "2") (pinfunction "2_2") (pintype "bidirectional"))
      (node (ref "U13") (pin "P$5") (pinfunction "AOUTR_P$5") (pintype "bidirectional"))
    )
    (net (code "93") (name "Net-(U14-BYPASS)") (class "Default")
      (node (ref "C51") (pin "2") (pinfunction "2_2") (pintype "bidirectional"))
      (node (ref "U14") (pin "3") (pinfunction "BYPASS_3") (pintype "bidirectional"))
    )
    (net (code "94") (name "Net-(U14-VIN1)") (class "Default")
      (node (ref "C52") (pin "2") (pinfunction "2_2") (pintype "bidirectional"))
      (node (ref "U14") (pin "2") (pinfunction "VIN1_2") (pintype "bidirectional"))
    )
    (net (code "95") (name "Net-(U14-VIN2)") (class "Default")
      (node (ref "C53") (pin "2") (pinfunction "2_2") (pintype "bidirectional"))
      (node (ref "U14") (pin "8") (pinfunction "VIN2_8") (pintype "bidirectional"))
    )
    (net (code "96") (name "Net-(U14-VOUT1)") (class "Default")
      (node (ref "C49") (pin "2") (pinfunction "2_2") (pintype "bidirectional"))
      (node (ref "U14") (pin "1") (pinfunction "VOUT1_1") (pintype "bidirectional"))
    )
    (net (code "97") (name "Net-(U14-VOUT2)") (class "Default")
      (node (ref "C50") (pin "2") (pinfunction "2_2") (pintype "bidirectional"))
      (node (ref "U14") (pin "9") (pinfunction "VOUT2_9") (pintype "bidirectional"))
    )
    (net (code "98") (name "Net-(U15-EN)") (class "Default")
      (node (ref "U15") (pin "3") (pinfunction "EN_3") (pintype "bidirectional"))
      (node (ref "U16") (pin "4") (pinfunction "Y_4") (pintype "bidirectional"))
    )
    (net (code "99") (name "unconnected-(J3-Pad3V3)") (class "Default")
      (node (ref "J3") (pin "3V3") (pinfunction "3V3_3V3") (pintype "bidirectional"))
    )
    (net (code "100") (name "unconnected-(J3-PadCS)") (class "Default")
      (node (ref "J3") (pin "CS") (pinfunction "CS_CS") (pintype "bidirectional"))
    )
    (net (code "101") (name "unconnected-(J3-PadDC)") (class "Default")
      (node (ref "J3") (pin "DC") (pinfunction "DC_DC") (pintype "bidirectional"))
    )
    (net (code "102") (name "unconnected-(J3-PadRST)") (class "Default")
      (node (ref "J3") (pin "RST") (pinfunction "RST_RST") (pintype "bidirectional"))
    )
    (net (code "103") (name "unconnected-(J4-DET_A-PadSW_A)") (class "Default")
      (node (ref "J4") (pin "SW_A") (pinfunction "DET_A_SW_A") (pintype "bidirectional"))
    )
    (net (code "104") (name "unconnected-(J4-DET_B-PadSW_B)") (class "Default")
      (node (ref "J4") (pin "SW_B") (pinfunction "DET_B_SW_B") (pintype "bidirectional"))
    )
    (net (code "105") (name "unconnected-(J4-PadDAT1)") (class "Default")
      (node (ref "J4") (pin "DAT1") (pinfunction "DAT1_DAT1") (pintype "bidirectional"))
    )
    (net (code "106") (name "unconnected-(J4-PadDAT2)") (class "Default")
      (node (ref "J4") (pin "DAT2") (pinfunction "DAT2_DAT2") (pintype "bidirectional"))
    )
    (net (code "107") (name "unconnected-(N1-PA3{slash}ADC3-Pad7)") (class "Default")
      (node (ref "N1") (pin "7") (pinfunction "PA3/ADC3_7") (pintype "bidirectional"))
    )
    (net (code "108") (name "unconnected-(N1-PA4{slash}ADC4-Pad6)") (class "Default")
      (node (ref "N1") (pin "6") (pinfunction "PA4/ADC4_6") (pintype "bidirectional"))
    )
    (net (code "109") (name "unconnected-(N1-PA5{slash}ADC5-Pad5)") (class "Default")
      (node (ref "N1") (pin "5") (pinfunction "PA5/ADC5_5") (pintype "bidirectional"))
    )
    (net (code "110") (name "unconnected-(N1-PA6{slash}ADC6-Pad4)") (class "Default")
      (node (ref "N1") (pin "4") (pinfunction "PA6/ADC6_4") (pintype "bidirectional"))
    )
    (net (code "111") (name "unconnected-(N1-PB0-Pad11)") (class "Default")
      (node (ref "N1") (pin "11") (pinfunction "PB0_11") (pintype "bidirectional"))
    )
    (net (code "112") (name "unconnected-(N1-PB1-Pad12)") (class "Default")
      (node (ref "N1") (pin "12") (pinfunction "PB1_12") (pintype "bidirectional"))
    )
    (net (code "113") (name "unconnected-(N1-PB2-Pad13)") (class "Default")
      (node (ref "N1") (pin "13") (pinfunction "PB2_13") (pintype "bidirectional"))
    )
    (net (code "114") (name "unconnected-(N1-PD7-Pad22)") (class "Default")
      (node (ref "N1") (pin "22") (pinfunction "PD7_22") (pintype "bidirectional"))
    )
    (net (code "115") (name "unconnected-(N1-VUSB-Pad2)") (class "Default")
      (node (ref "N1") (pin "2") (pinfunction "VUSB_2") (pintype "bidirectional"))
    )
    (net (code "116") (name "unconnected-(N1-~{RST}-Pad34)") (class "Default")
      (node (ref "N1") (pin "34") (pinfunction "~{RST}_34") (pintype "bidirectional"))
    )
    (net (code "117") (name "unconnected-(S1-3-Pad1)") (class "Default")
      (node (ref "S1") (pin "1") (pinfunction "3_1") (pintype "bidirectional"))
    )
    (net (code "118") (name "unconnected-(U1-ADC-PadP$25)") (class "Default")
      (node (ref "U1") (pin "P$25") (pinfunction "ADC_P$25") (pintype "bidirectional"))
    )
    (net (code "119") (name "unconnected-(U1-CTS-PadP$7)") (class "Default")
      (node (ref "U1") (pin "P$7") (pinfunction "CTS_P$7") (pintype "bidirectional"))
    )
    (net (code "120") (name "unconnected-(U1-DCD-PadP$5)") (class "Default")
      (node (ref "U1") (pin "P$5") (pinfunction "DCD_P$5") (pintype "bidirectional"))
    )
    (net (code "121") (name "unconnected-(U1-DTR-PadP$3)") (class "Default")
      (node (ref "U1") (pin "P$3") (pinfunction "DTR_P$3") (pintype "bidirectional"))
    )
    (net (code "122") (name "unconnected-(U1-GPIO1-PadP$40)") (class "Default")
      (node (ref "U1") (pin "P$40") (pinfunction "GPIO1_P$40") (pintype "bidirectional"))
    )
    (net (code "123") (name "unconnected-(U1-GPIO2-PadP$41)") (class "Default")
      (node (ref "U1") (pin "P$41") (pinfunction "GPIO2_P$41") (pintype "bidirectional"))
    )
    (net (code "124") (name "unconnected-(U1-GPIO3-PadP$42)") (class "Default")
      (node (ref "U1") (pin "P$42") (pinfunction "GPIO3_P$42") (pintype "bidirectional"))
    )
    (net (code "125") (name "unconnected-(U1-GPIO4-PadP$43)") (class "Default")
      (node (ref "U1") (pin "P$43") (pinfunction "GPIO4_P$43") (pintype "bidirectional"))
    )
    (net (code "126") (name "unconnected-(U1-GPIO6-PadP$47)") (class "Default")
      (node (ref "U1") (pin "P$47") (pinfunction "GPIO6_P$47") (pintype "bidirectional"))
    )
    (net (code "127") (name "unconnected-(U1-GPIO7-PadP$48)") (class "Default")
      (node (ref "U1") (pin "P$48") (pinfunction "GPIO7_P$48") (pintype "bidirectional"))
    )
    (net (code "128") (name "unconnected-(U1-GPIO8{slash}DBG_RXD-PadP$49)") (class "Default")
      (node (ref "U1") (pin "P$49") (pinfunction "GPIO8/DBG_RXD_P$49") (pintype "bidirectional"))
    )
    (net (code "129") (name "unconnected-(U1-GPIO9{slash}DBG_TXD-PadP$50)") (class "Default")
      (node (ref "U1") (pin "P$50") (pinfunction "GPIO9/DBG_TXD_P$50") (pintype "bidirectional"))
    )
    (net (code "130") (name "unconnected-(U1-GPIO11-PadP$67)") (class "Default")
      (node (ref "U1") (pin "P$67") (pinfunction "GPIO11_P$67") (pintype "bidirectional"))
    )
    (net (code "131") (name "unconnected-(U1-GPIO12-PadP$68)") (class "Default")
      (node (ref "U1") (pin "P$68") (pinfunction "GPIO12_P$68") (pintype "bidirectional"))
    )
    (net (code "132") (name "unconnected-(U1-NETLIGHT-PadP$52)") (class "Default")
      (node (ref "U1") (pin "P$52") (pinfunction "NETLIGHT_P$52") (pintype "bidirectional"))
    )
    (net (code "133") (name "unconnected-(U1-PWM1-PadP$35)") (class "Default")
      (node (ref "U1") (pin "P$35") (pinfunction "PWM1_P$35") (pintype "bidirectional"))
    )
    (net (code "134") (name "unconnected-(U1-PWM2-PadP$36)") (class "Default")
      (node (ref "U1") (pin "P$36") (pinfunction "PWM2_P$36") (pintype "bidirectional"))
    )
    (net (code "135") (name "unconnected-(U1-RESET-PadP$16)") (class "Default")
      (node (ref "U1") (pin "P$16") (pinfunction "RESET_P$16") (pintype "bidirectional"))
    )
    (net (code "136") (name "unconnected-(U1-RTS-PadP$8)") (class "Default")
      (node (ref "U1") (pin "P$8") (pinfunction "RTS_P$8") (pintype "bidirectional"))
    )
    (net (code "137") (name "unconnected-(U1-SCL-PadP$38)") (class "Default")
      (node (ref "U1") (pin "P$38") (pinfunction "SCL_P$38") (pintype "bidirectional"))
    )
    (net (code "138") (name "unconnected-(U1-SDA-PadP$37)") (class "Default")
      (node (ref "U1") (pin "P$37") (pinfunction "SDA_P$37") (pintype "bidirectional"))
    )
    (net (code "139") (name "unconnected-(U1-SPI_CLK-PadP$11)") (class "Default")
      (node (ref "U1") (pin "P$11") (pinfunction "SPI_CLK_P$11") (pintype "bidirectional"))
    )
    (net (code "140") (name "unconnected-(U1-SPI_CS-PadP$14)") (class "Default")
      (node (ref "U1") (pin "P$14") (pinfunction "SPI_CS_P$14") (pintype "bidirectional"))
    )
    (net (code "141") (name "unconnected-(U1-SPI_MISO-PadP$13)") (class "Default")
      (node (ref "U1") (pin "P$13") (pinfunction "SPI_MISO_P$13") (pintype "bidirectional"))
    )
    (net (code "142") (name "unconnected-(U1-SPI_MOSI-PadP$12)") (class "Default")
      (node (ref "U1") (pin "P$12") (pinfunction "SPI_MOSI_P$12") (pintype "bidirectional"))
    )
    (net (code "143") (name "unconnected-(U1-USB_DN-PadP$28)") (class "Default")
      (node (ref "U1") (pin "P$28") (pinfunction "USB_DN_P$28") (pintype "bidirectional"))
    )
    (net (code "144") (name "unconnected-(U1-USB_DP-PadP$27)") (class "Default")
      (node (ref "U1") (pin "P$27") (pinfunction "USB_DP_P$27") (pintype "bidirectional"))
    )
    (net (code "145") (name "unconnected-(U1-USIM_DET-PadP$34)") (class "Default")
      (node (ref "U1") (pin "P$34") (pinfunction "USIM_DET_P$34") (pintype "bidirectional"))
    )
    (net (code "146") (name "unconnected-(U1-VBUS-PadP$24)") (class "Default")
      (node (ref "U1") (pin "P$24") (pinfunction "VBUS_P$24") (pintype "bidirectional"))
    )
    (net (code "147") (name "unconnected-(U1-VRTC-PadP$26)") (class "Default")
      (node (ref "U1") (pin "P$26") (pinfunction "VRTC_P$26") (pintype "bidirectional"))
    )
    (net (code "148") (name "unconnected-(U3-INT-Pad7)") (class "Default")
      (node (ref "U3") (pin "7") (pinfunction "INT_7") (pintype "bidirectional"))
    )
    (net (code "149") (name "unconnected-(U4-INT-Pad7)") (class "Default")
      (node (ref "U4") (pin "7") (pinfunction "INT_7") (pintype "bidirectional"))
    )
    (net (code "150") (name "unconnected-(U5-GP5-Pad14)") (class "Default")
      (node (ref "U5") (pin "14") (pinfunction "GP5_14") (pintype "bidirectional"))
    )
    (net (code "151") (name "unconnected-(U5-GP6-Pad15)") (class "Default")
      (node (ref "U5") (pin "15") (pinfunction "GP6_15") (pintype "bidirectional"))
    )
    (net (code "152") (name "unconnected-(U5-GP7-Pad16)") (class "Default")
      (node (ref "U5") (pin "16") (pinfunction "GP7_16") (pintype "bidirectional"))
    )
    (net (code "153") (name "unconnected-(U5-INT-Pad7)") (class "Default")
      (node (ref "U5") (pin "7") (pinfunction "INT_7") (pintype "bidirectional"))
    )
    (net (code "154") (name "unconnected-(U8-VPP-PadC6)") (class "Default")
      (node (ref "U8") (pin "C6") (pinfunction "VPP_C6") (pintype "bidirectional"))
    )
    (net (code "155") (name "unconnected-(U9-X1-PadP$1)") (class "Default")
      (node (ref "U9") (pin "P$1") (pinfunction "X1_P$1") (pintype "bidirectional"))
    )
    (net (code "156") (name "unconnected-(U10-NC-Pad4)") (class "Default")
      (node (ref "U10") (pin "4") (pinfunction "NC_4") (pintype "bidirectional"))
    )
    (net (code "157") (name "unconnected-(U11-NC-Pad2)") (class "Default")
      (node (ref "U11") (pin "2") (pinfunction "NC_2") (pintype "bidirectional"))
    )
    (net (code "158") (name "unconnected-(U11-PG-Pad3)") (class "Default")
      (node (ref "U11") (pin "3") (pinfunction "PG_3") (pintype "bidirectional"))
    )
    (net (code "159") (name "unconnected-(U15-NC-Pad4)") (class "Default")
      (node (ref "U15") (pin "4") (pinfunction "NC_4") (pintype "bidirectional"))
    )
  )
)
